# INNO_CAN_V1_1.net
KiCad netlist of a schematic drawn in EAGLE
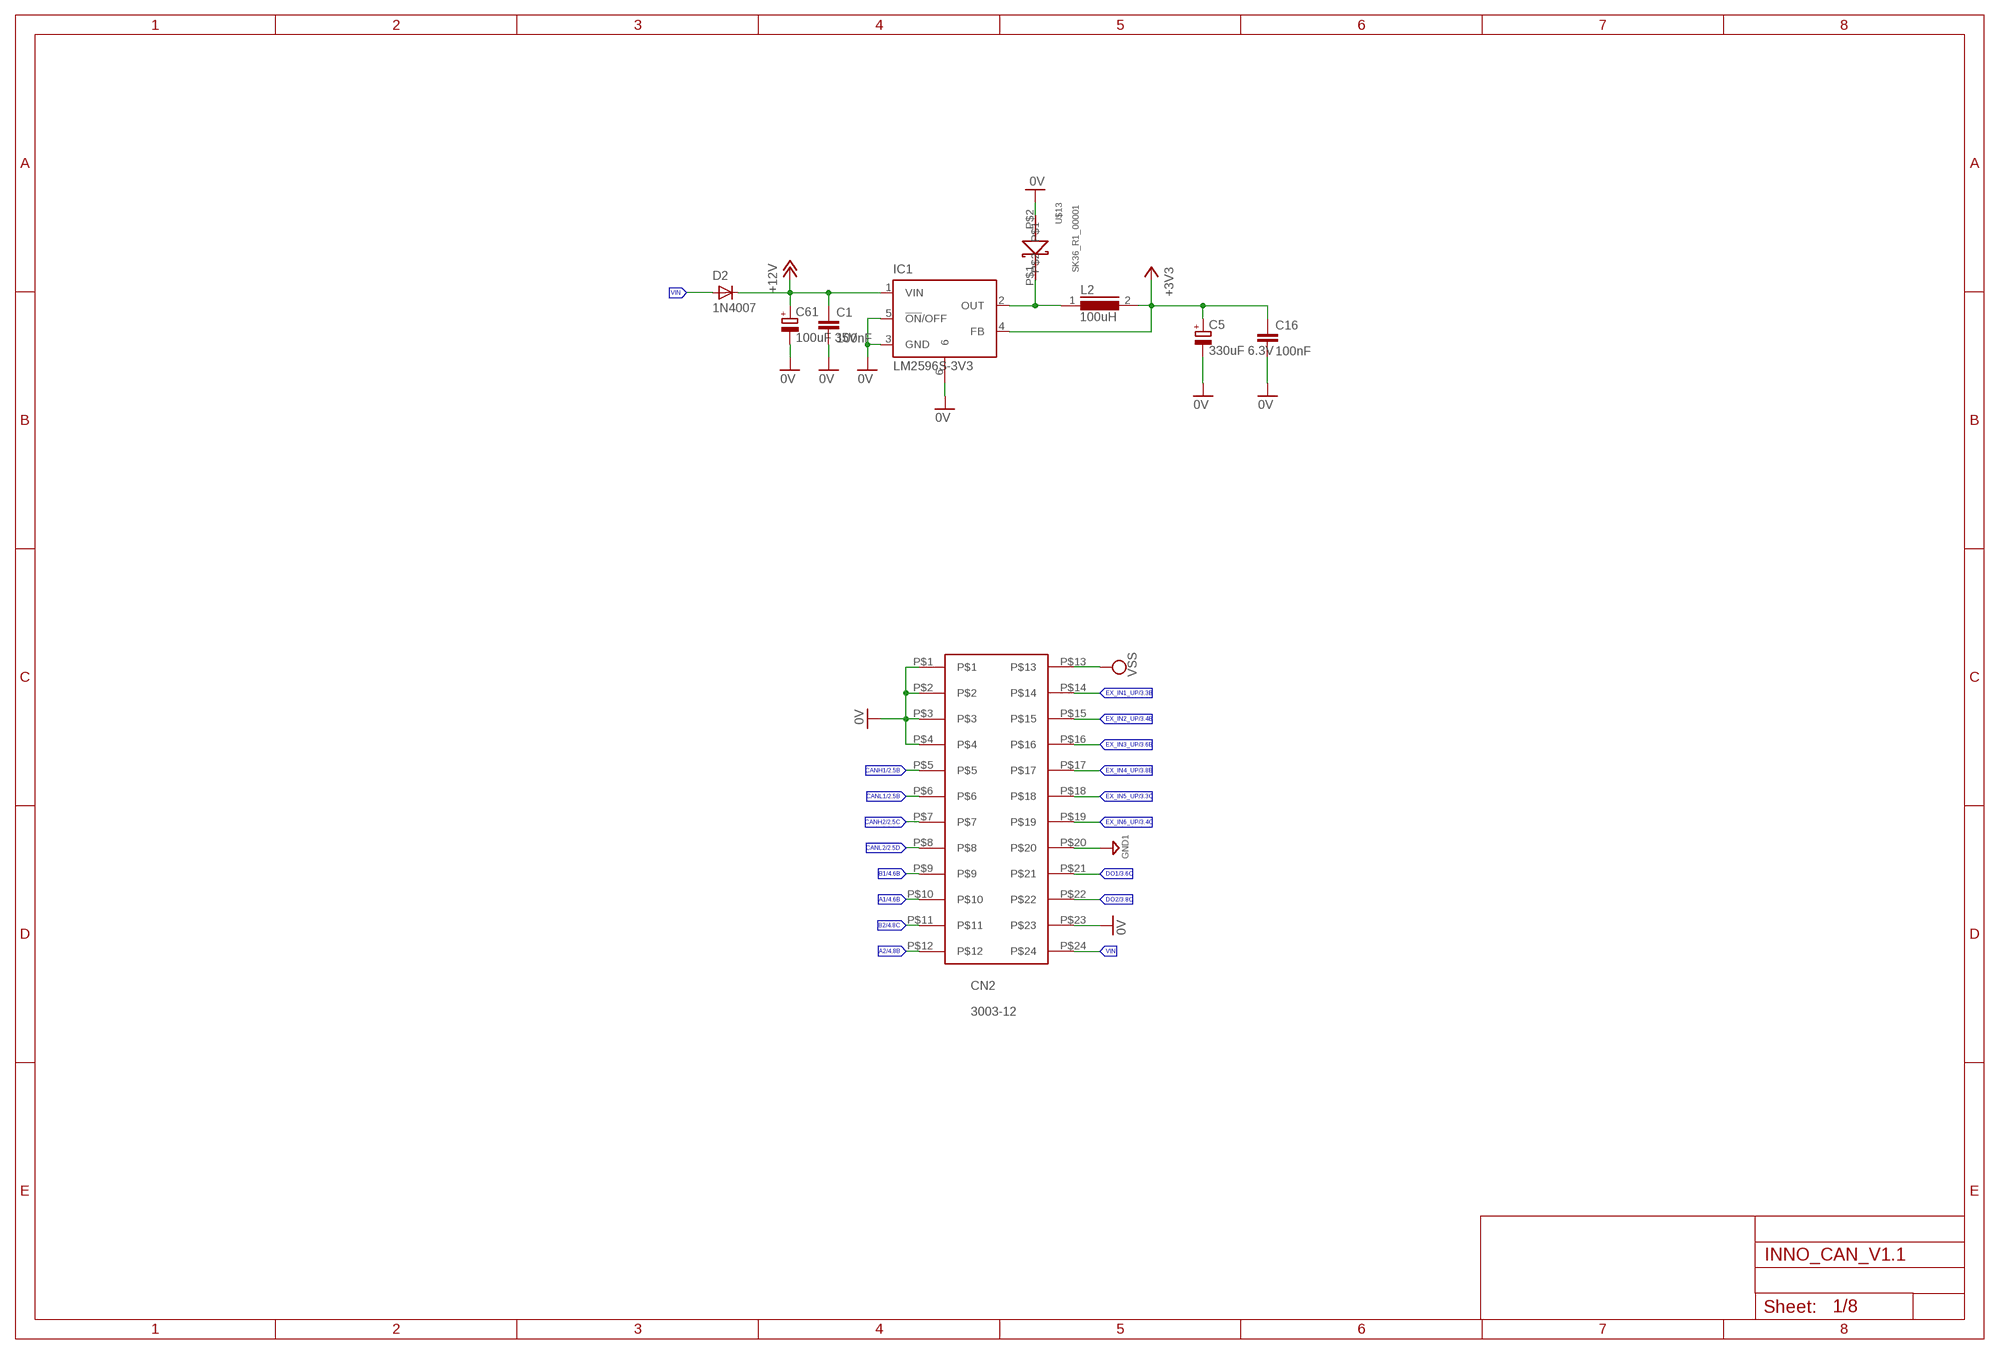
[diagram p0: schematic, sheet 1]
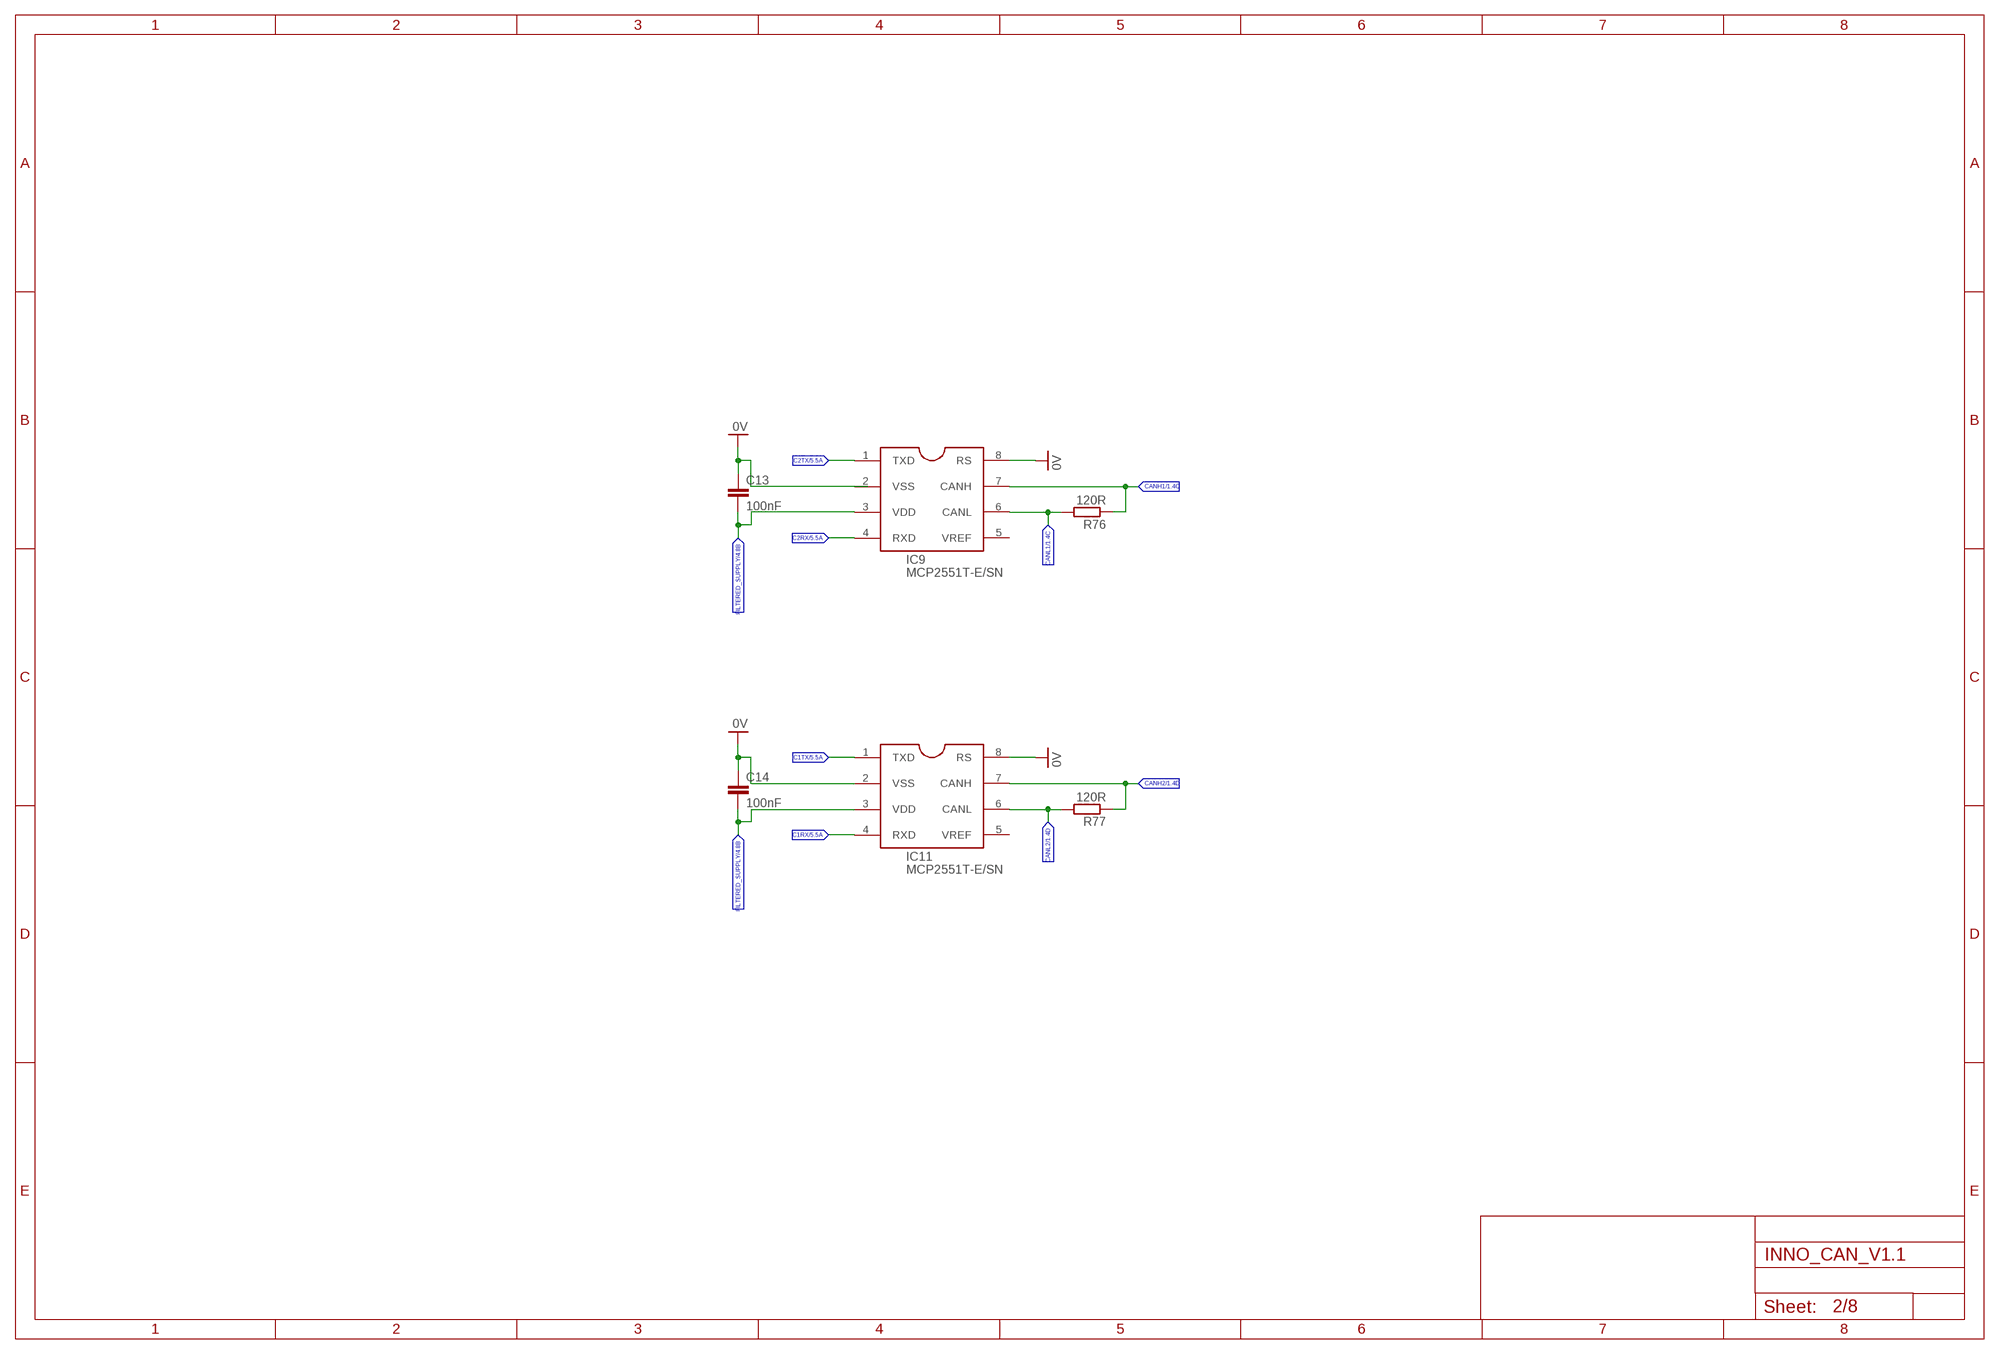
[diagram p1: schematic, sheet 2]
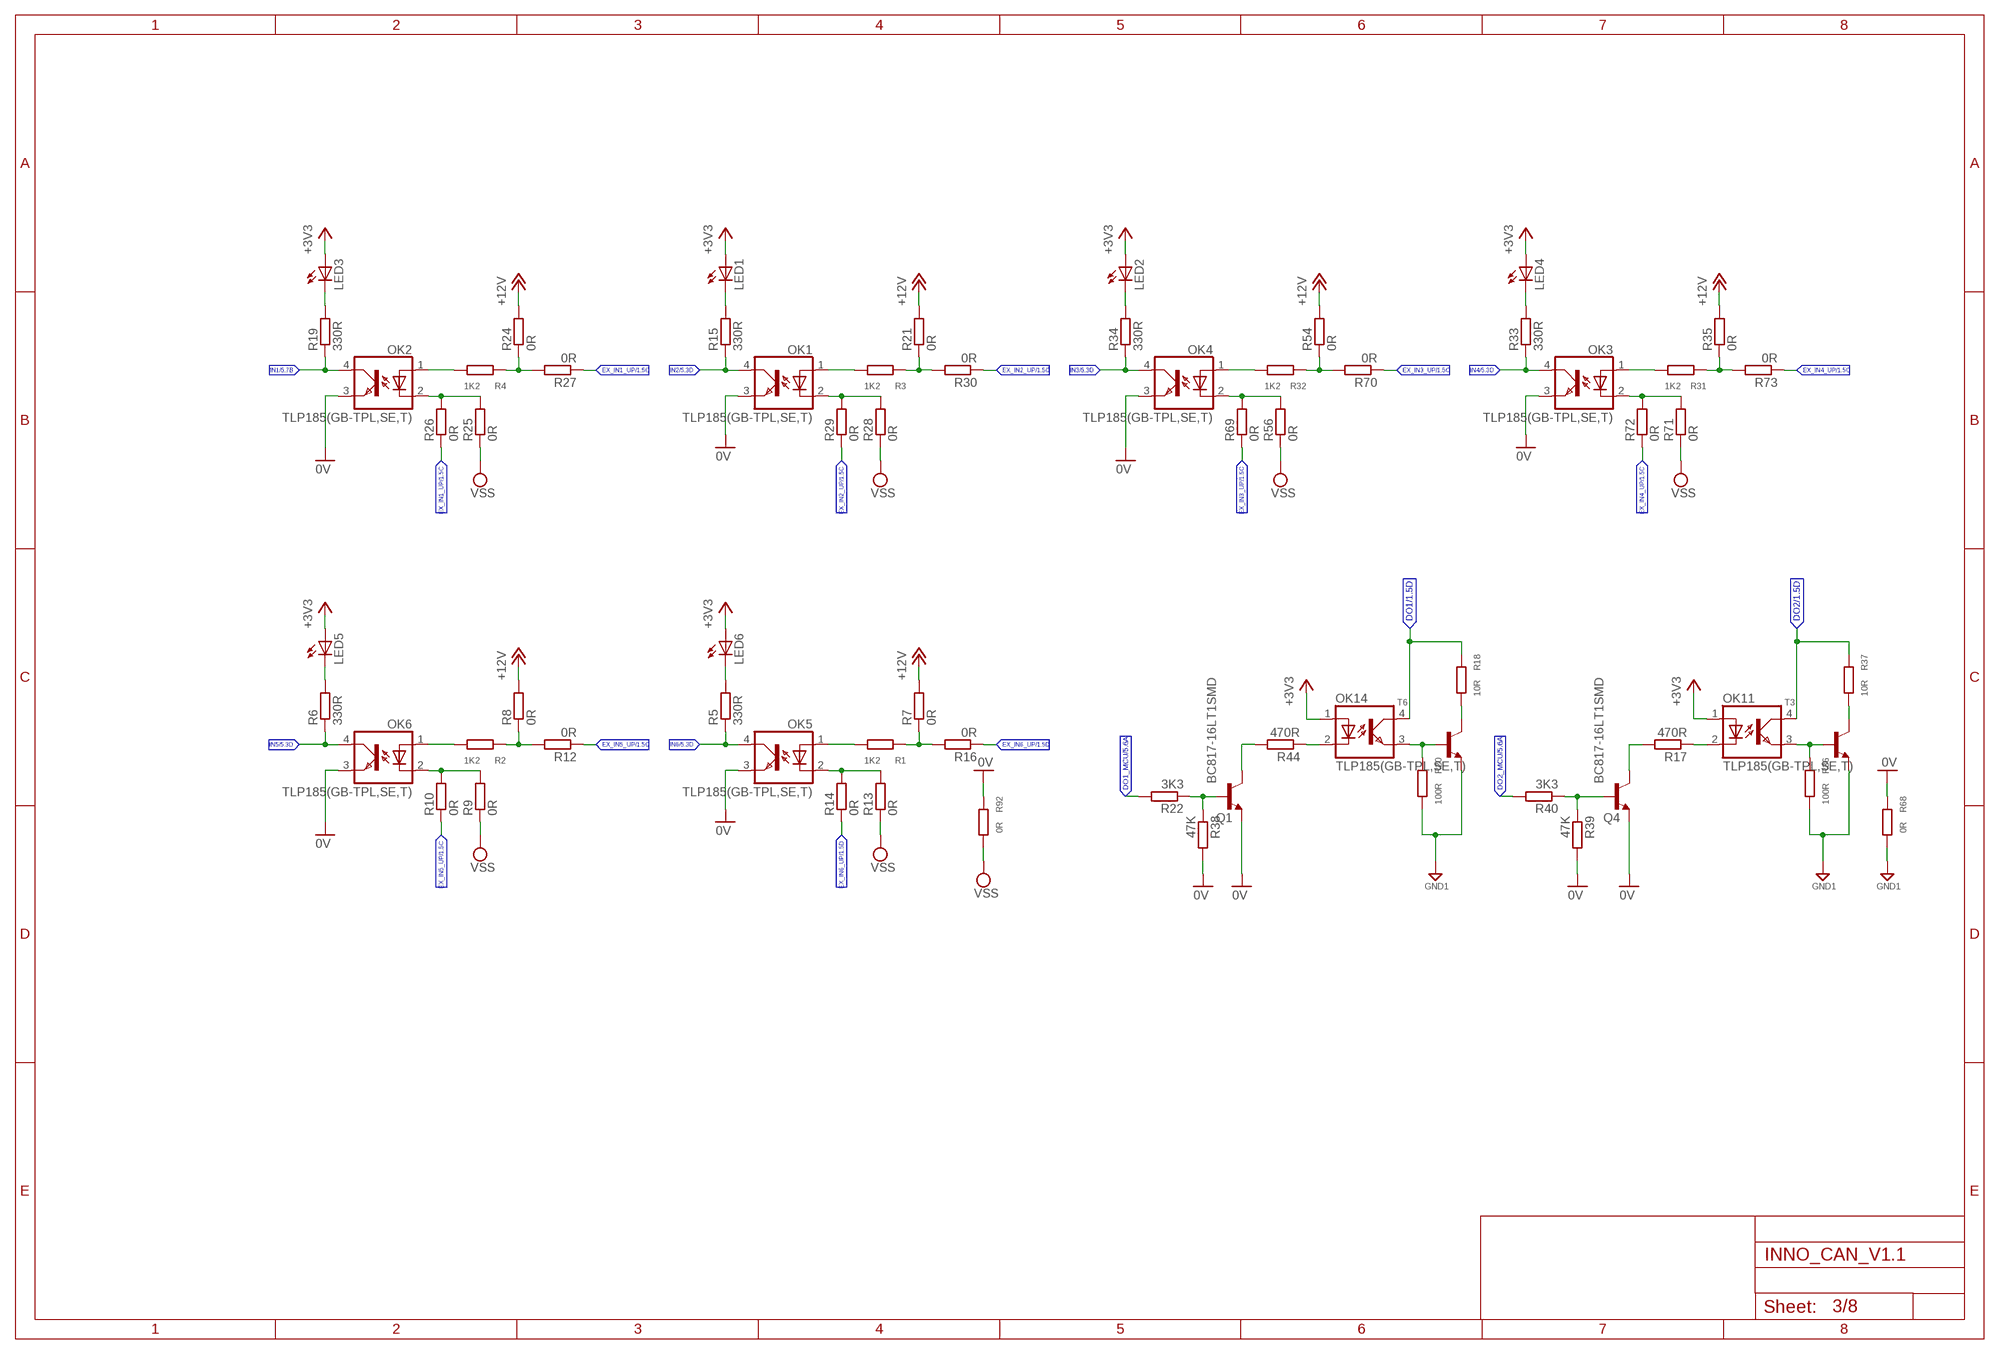
[diagram p2: schematic, sheet 3]
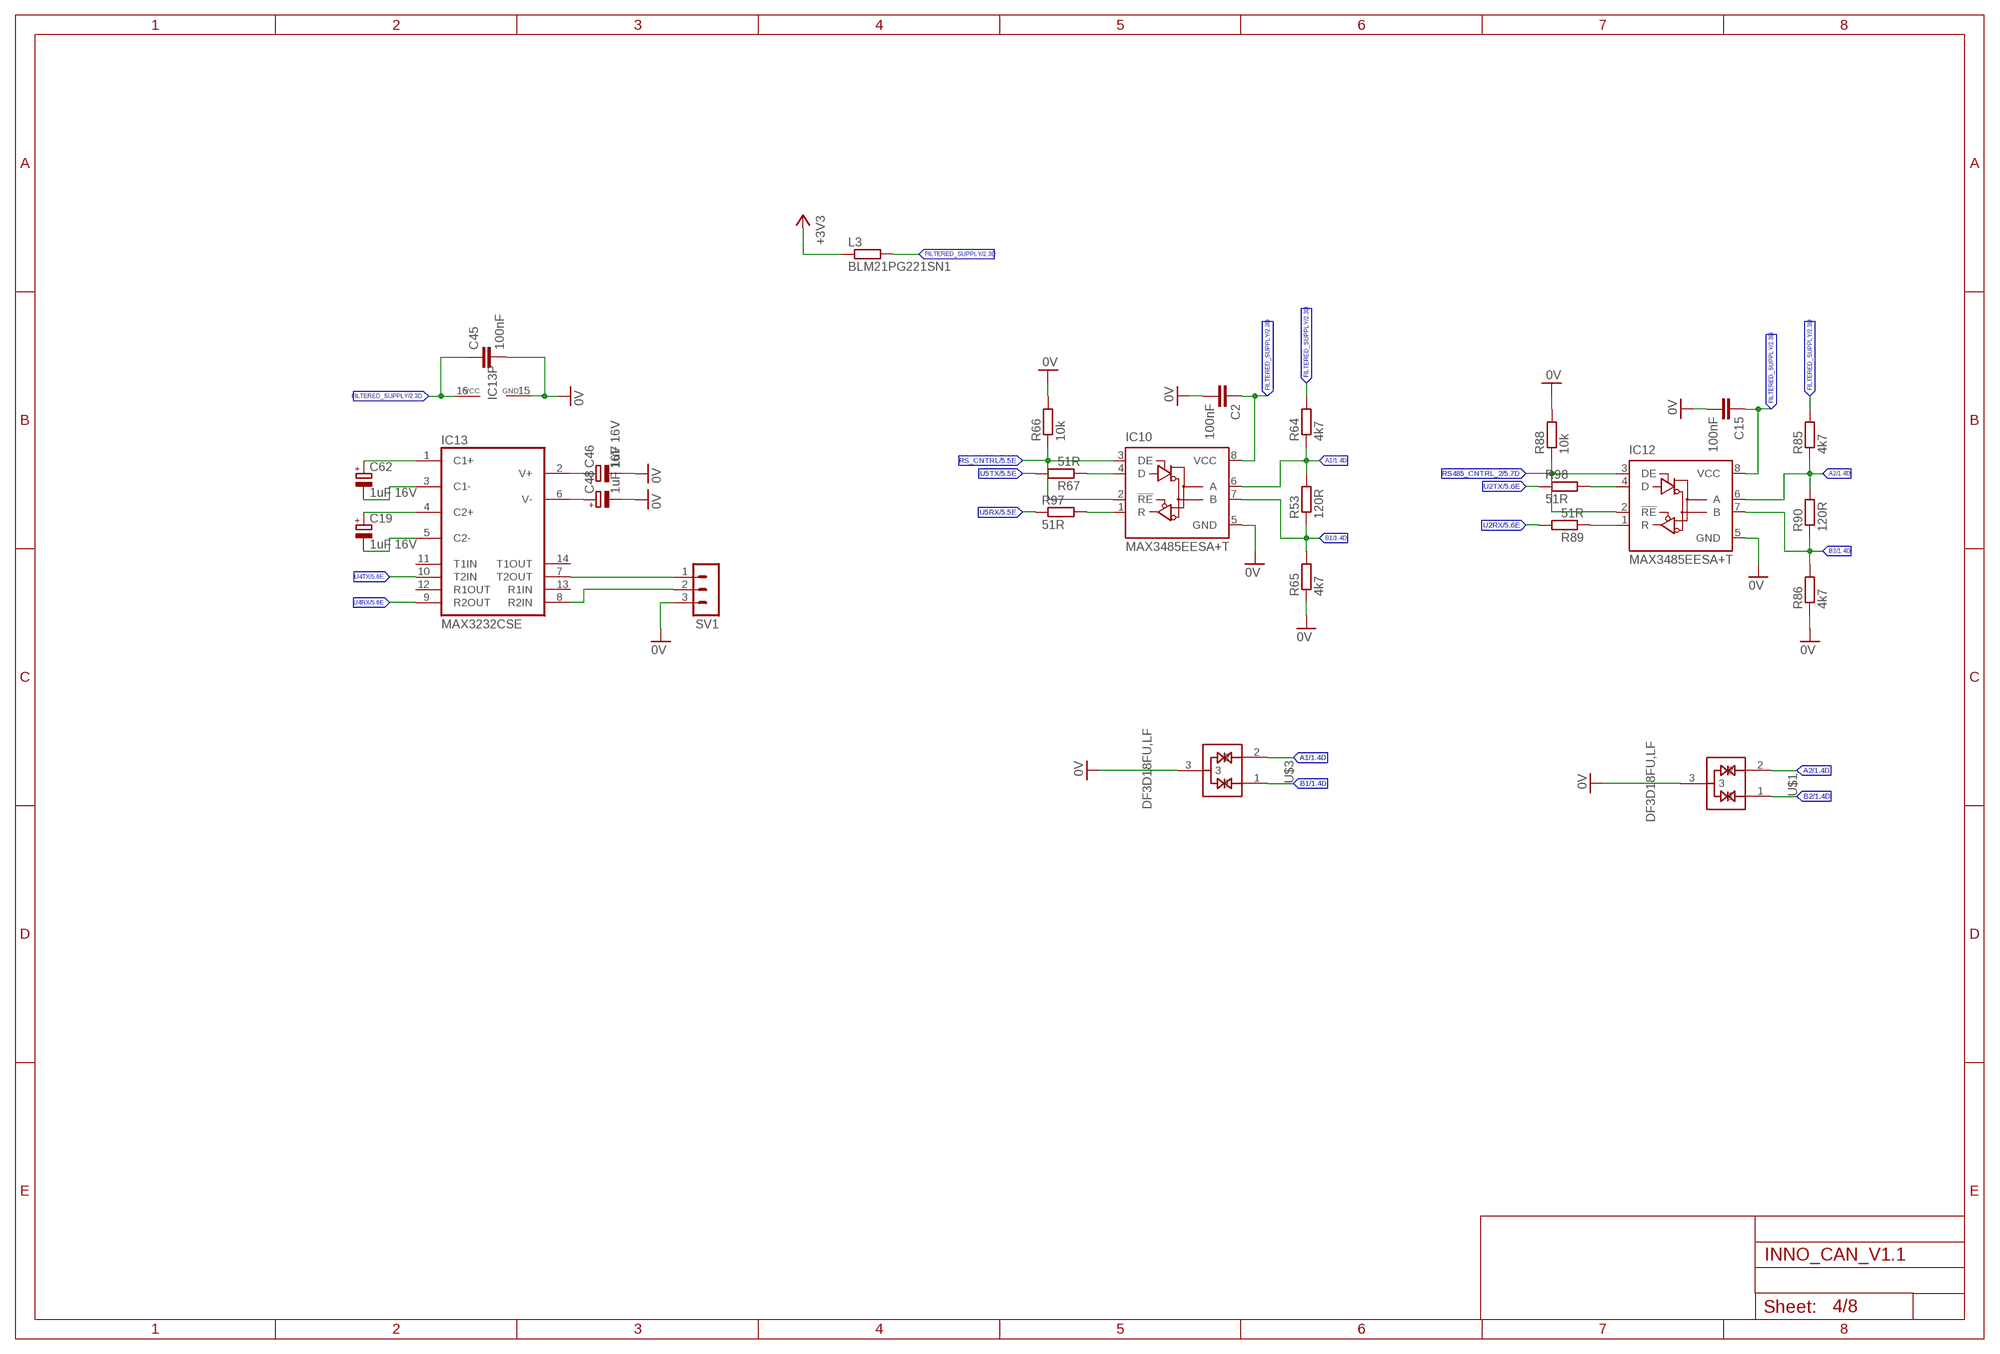
[diagram p3: schematic, sheet 4]
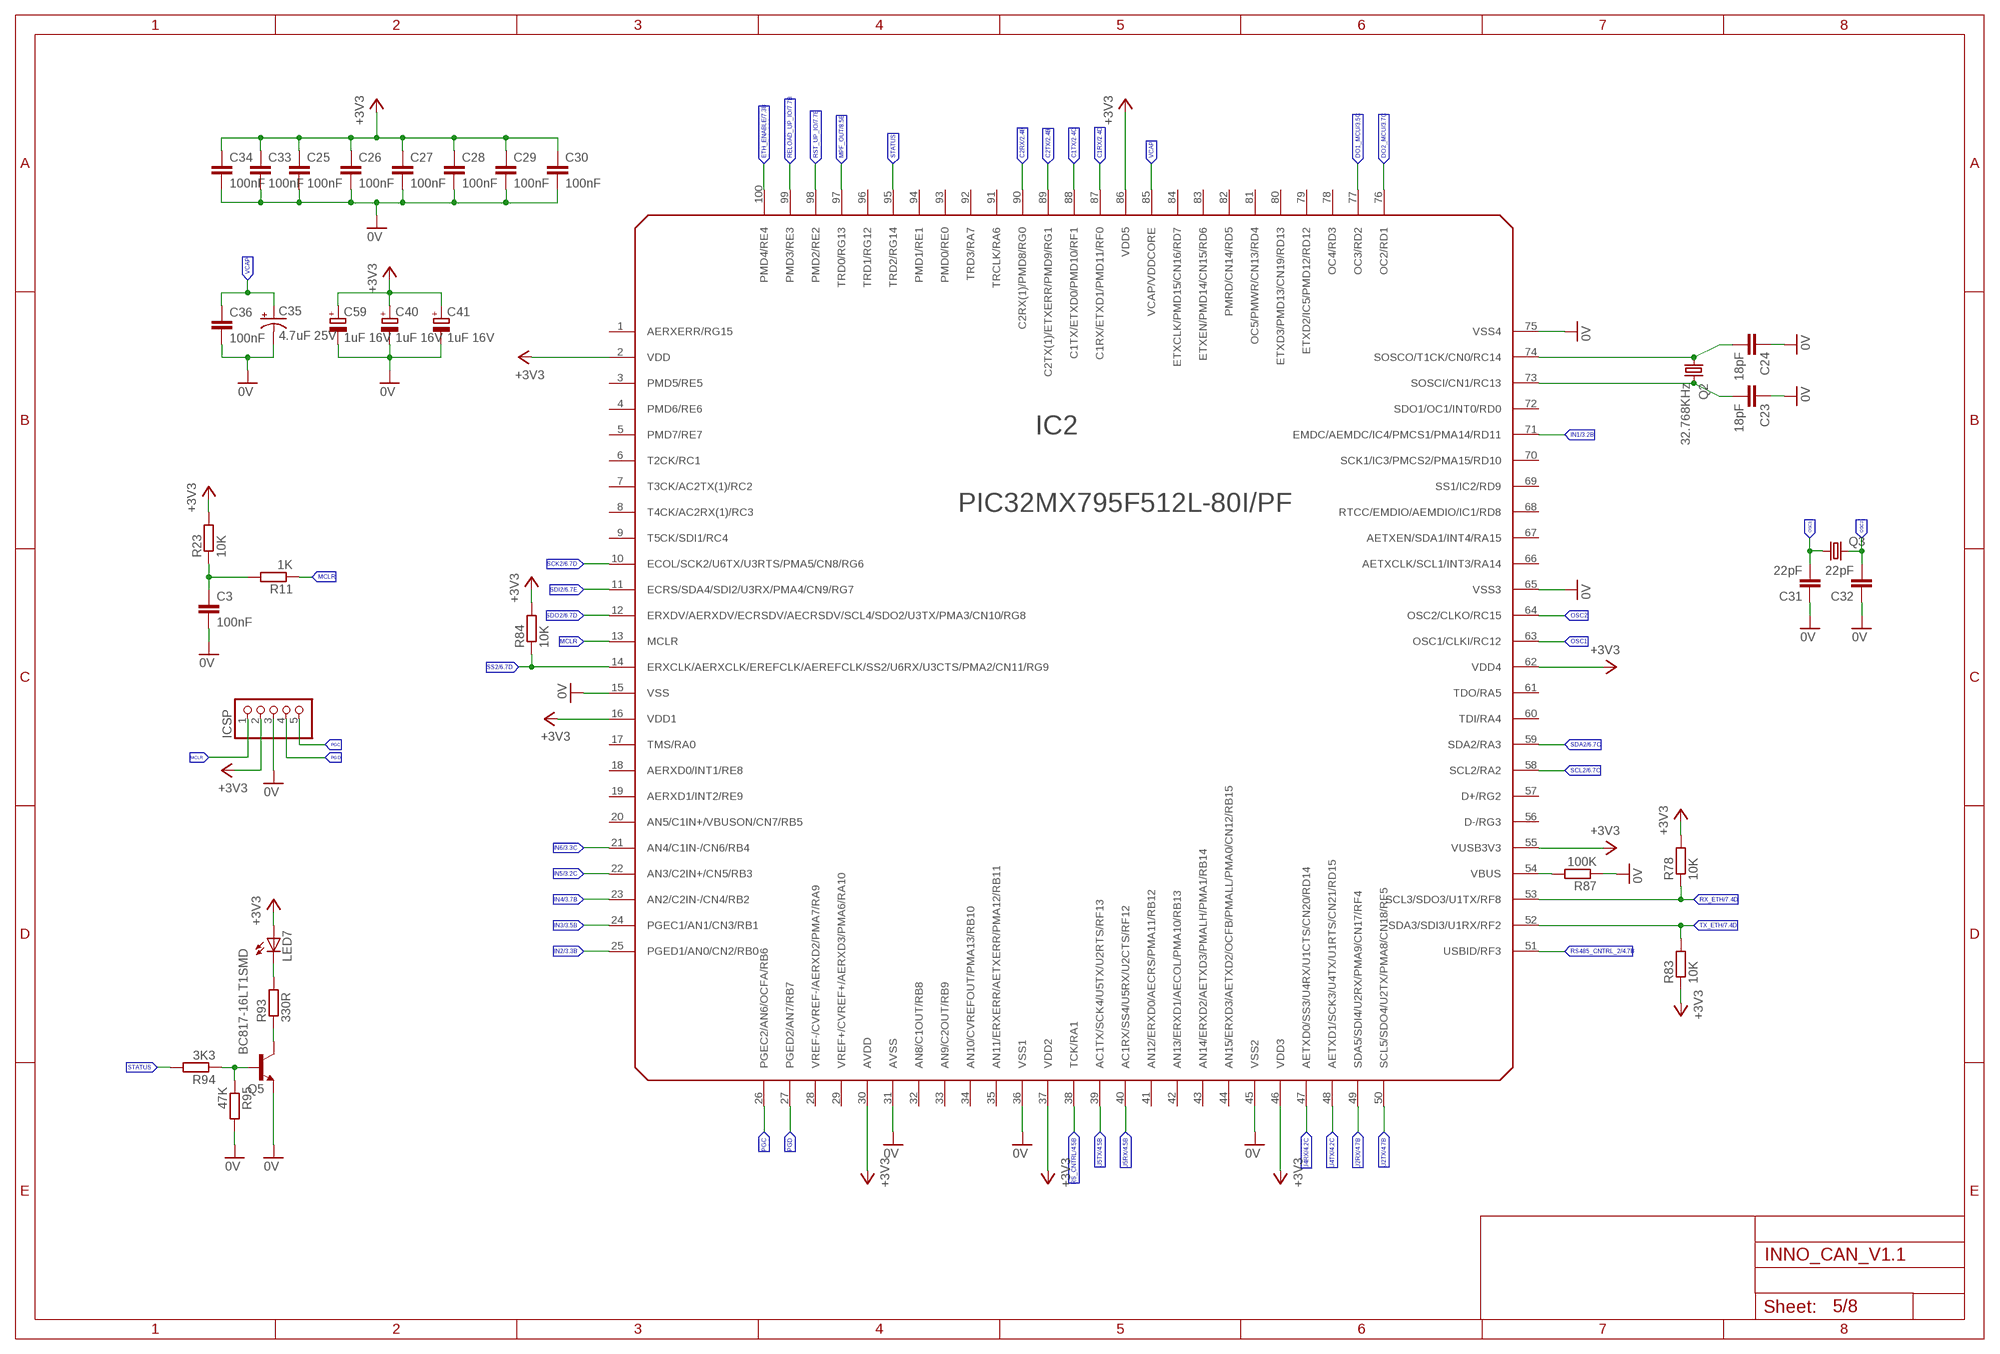
[diagram p4: schematic, sheet 5]
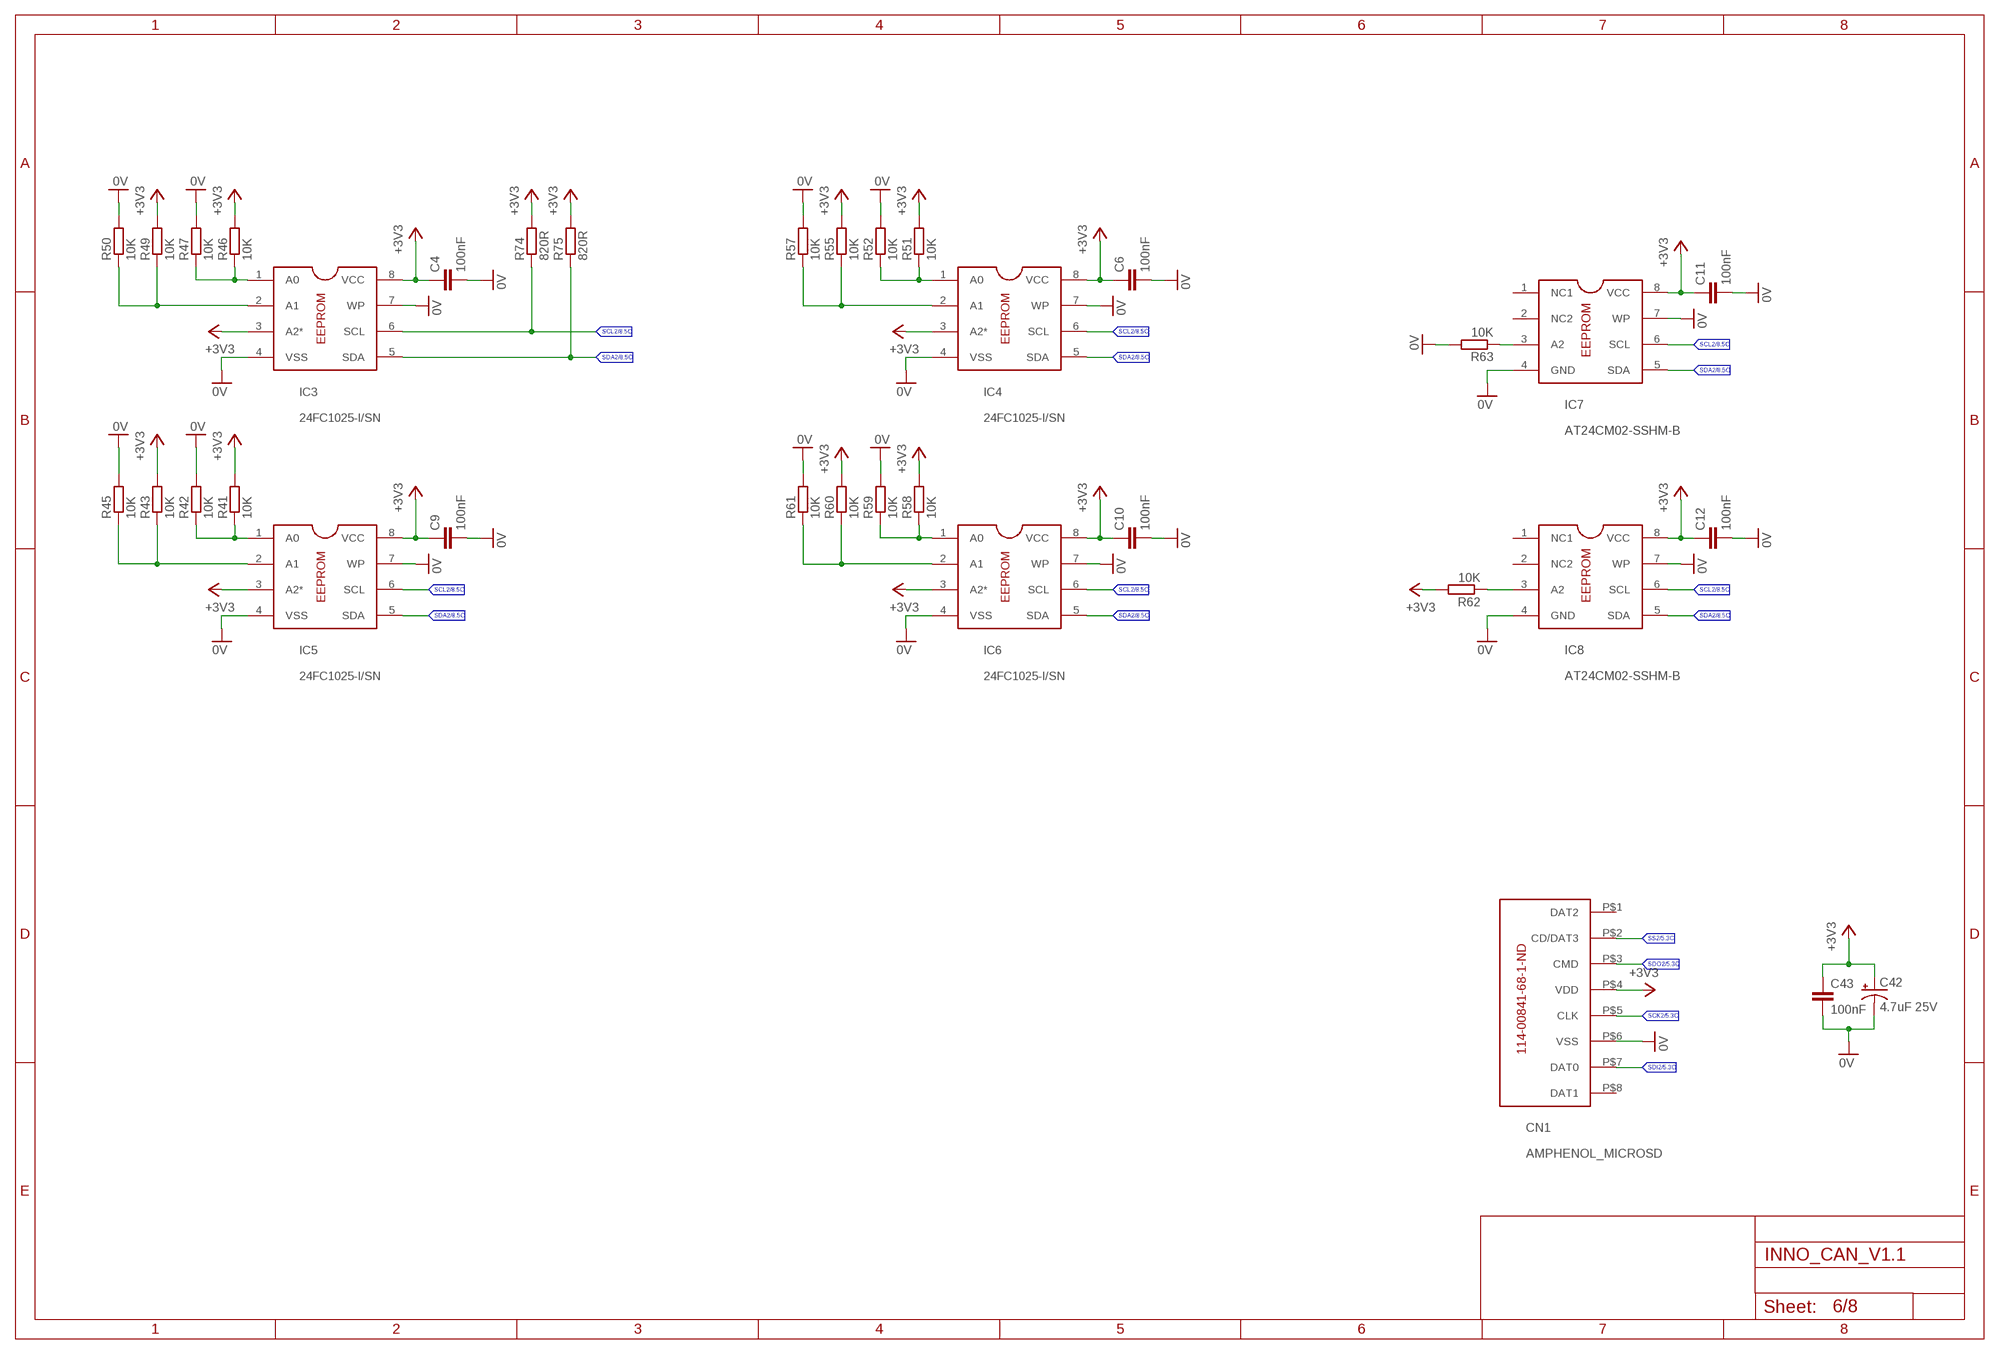
[diagram p5: schematic, sheet 6]
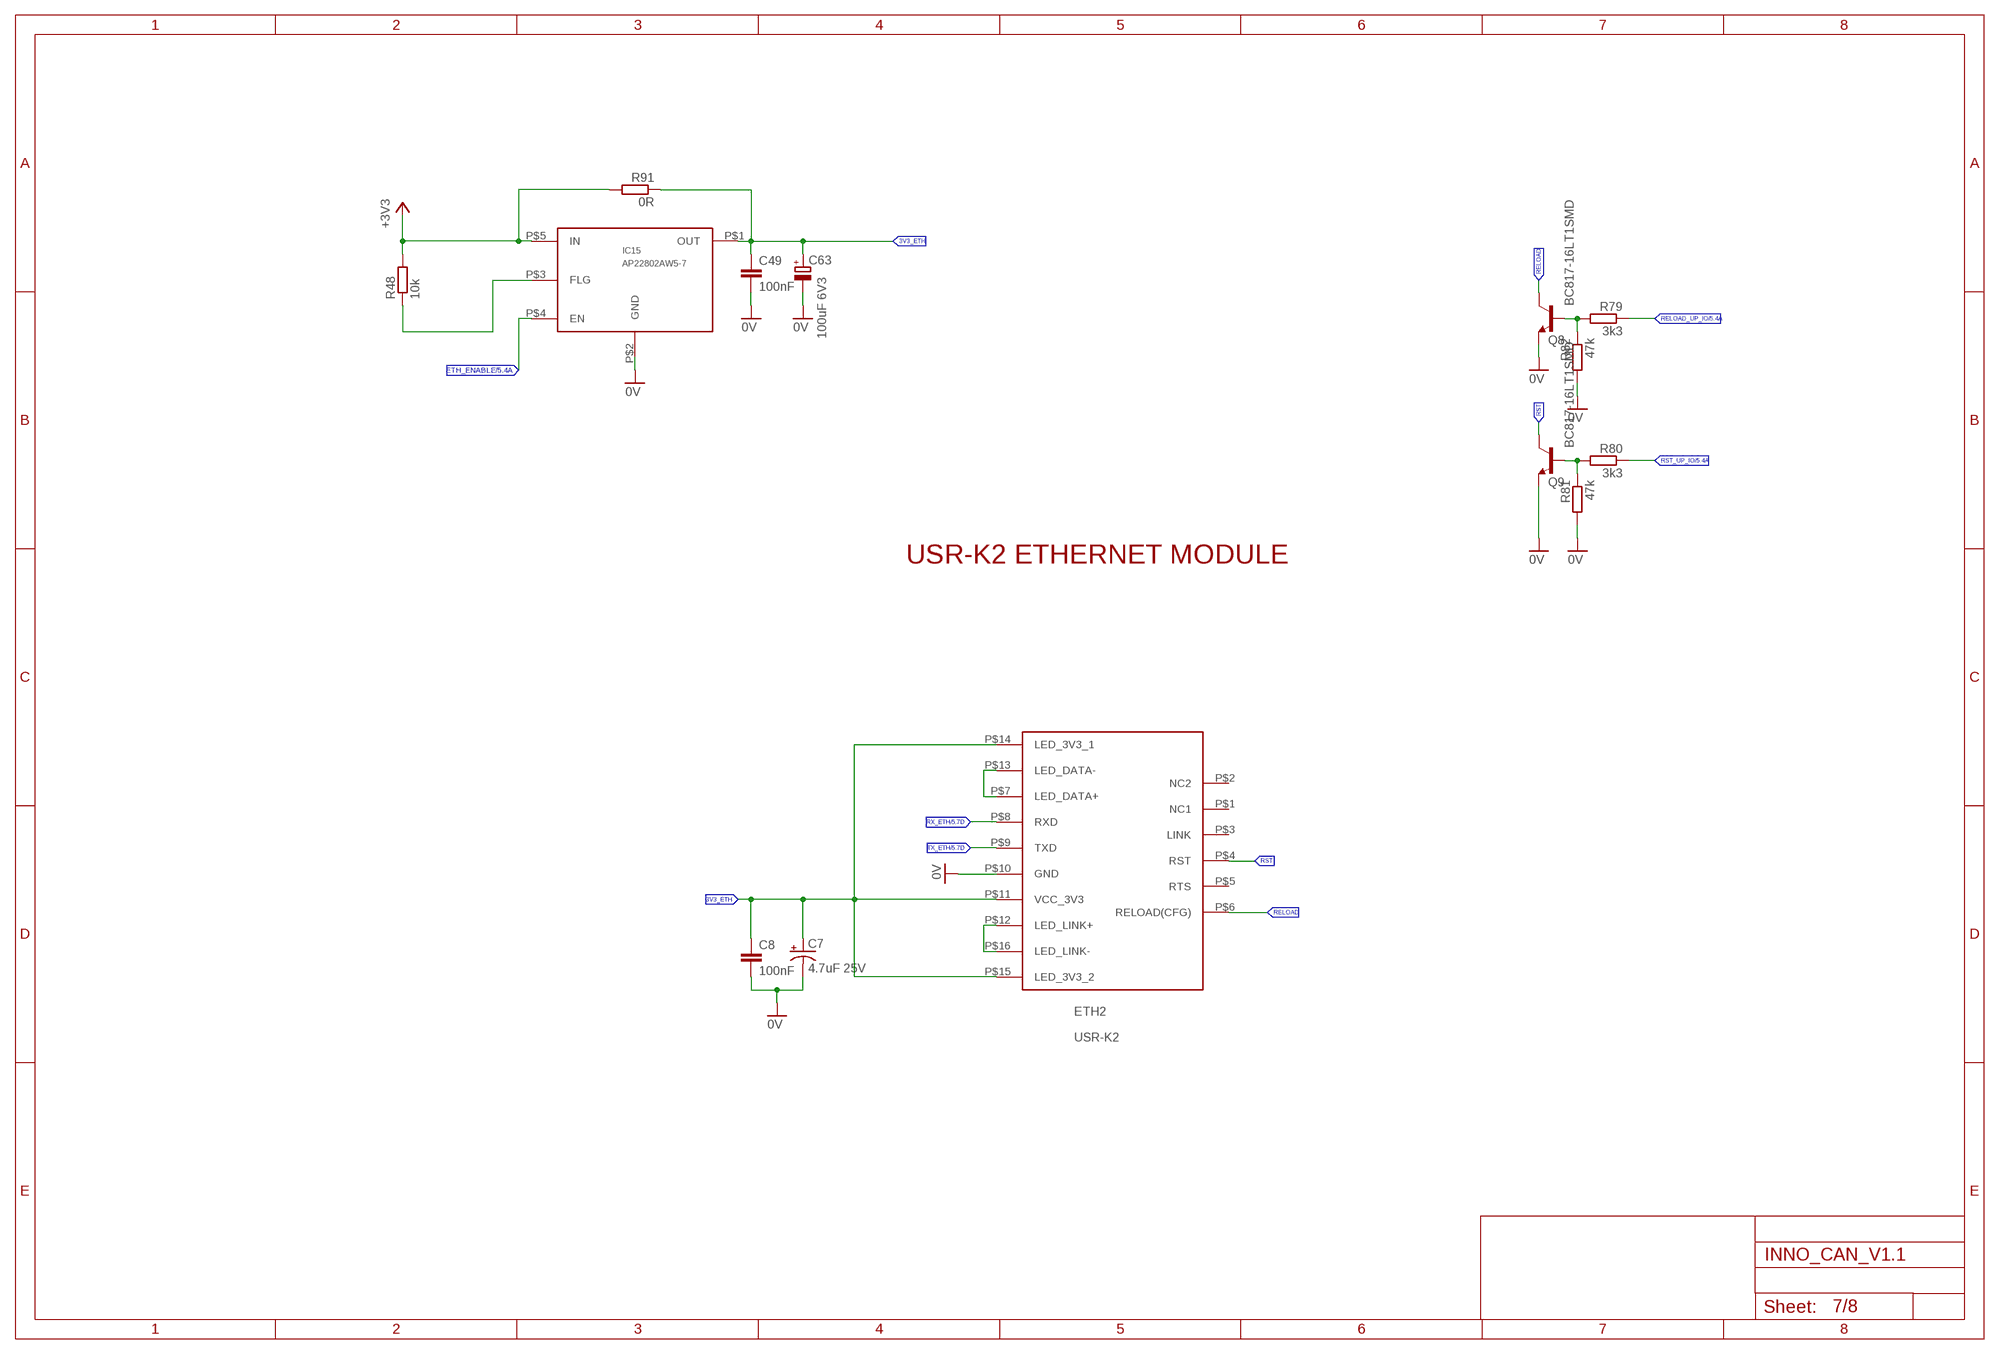
[diagram p6: schematic, sheet 7]
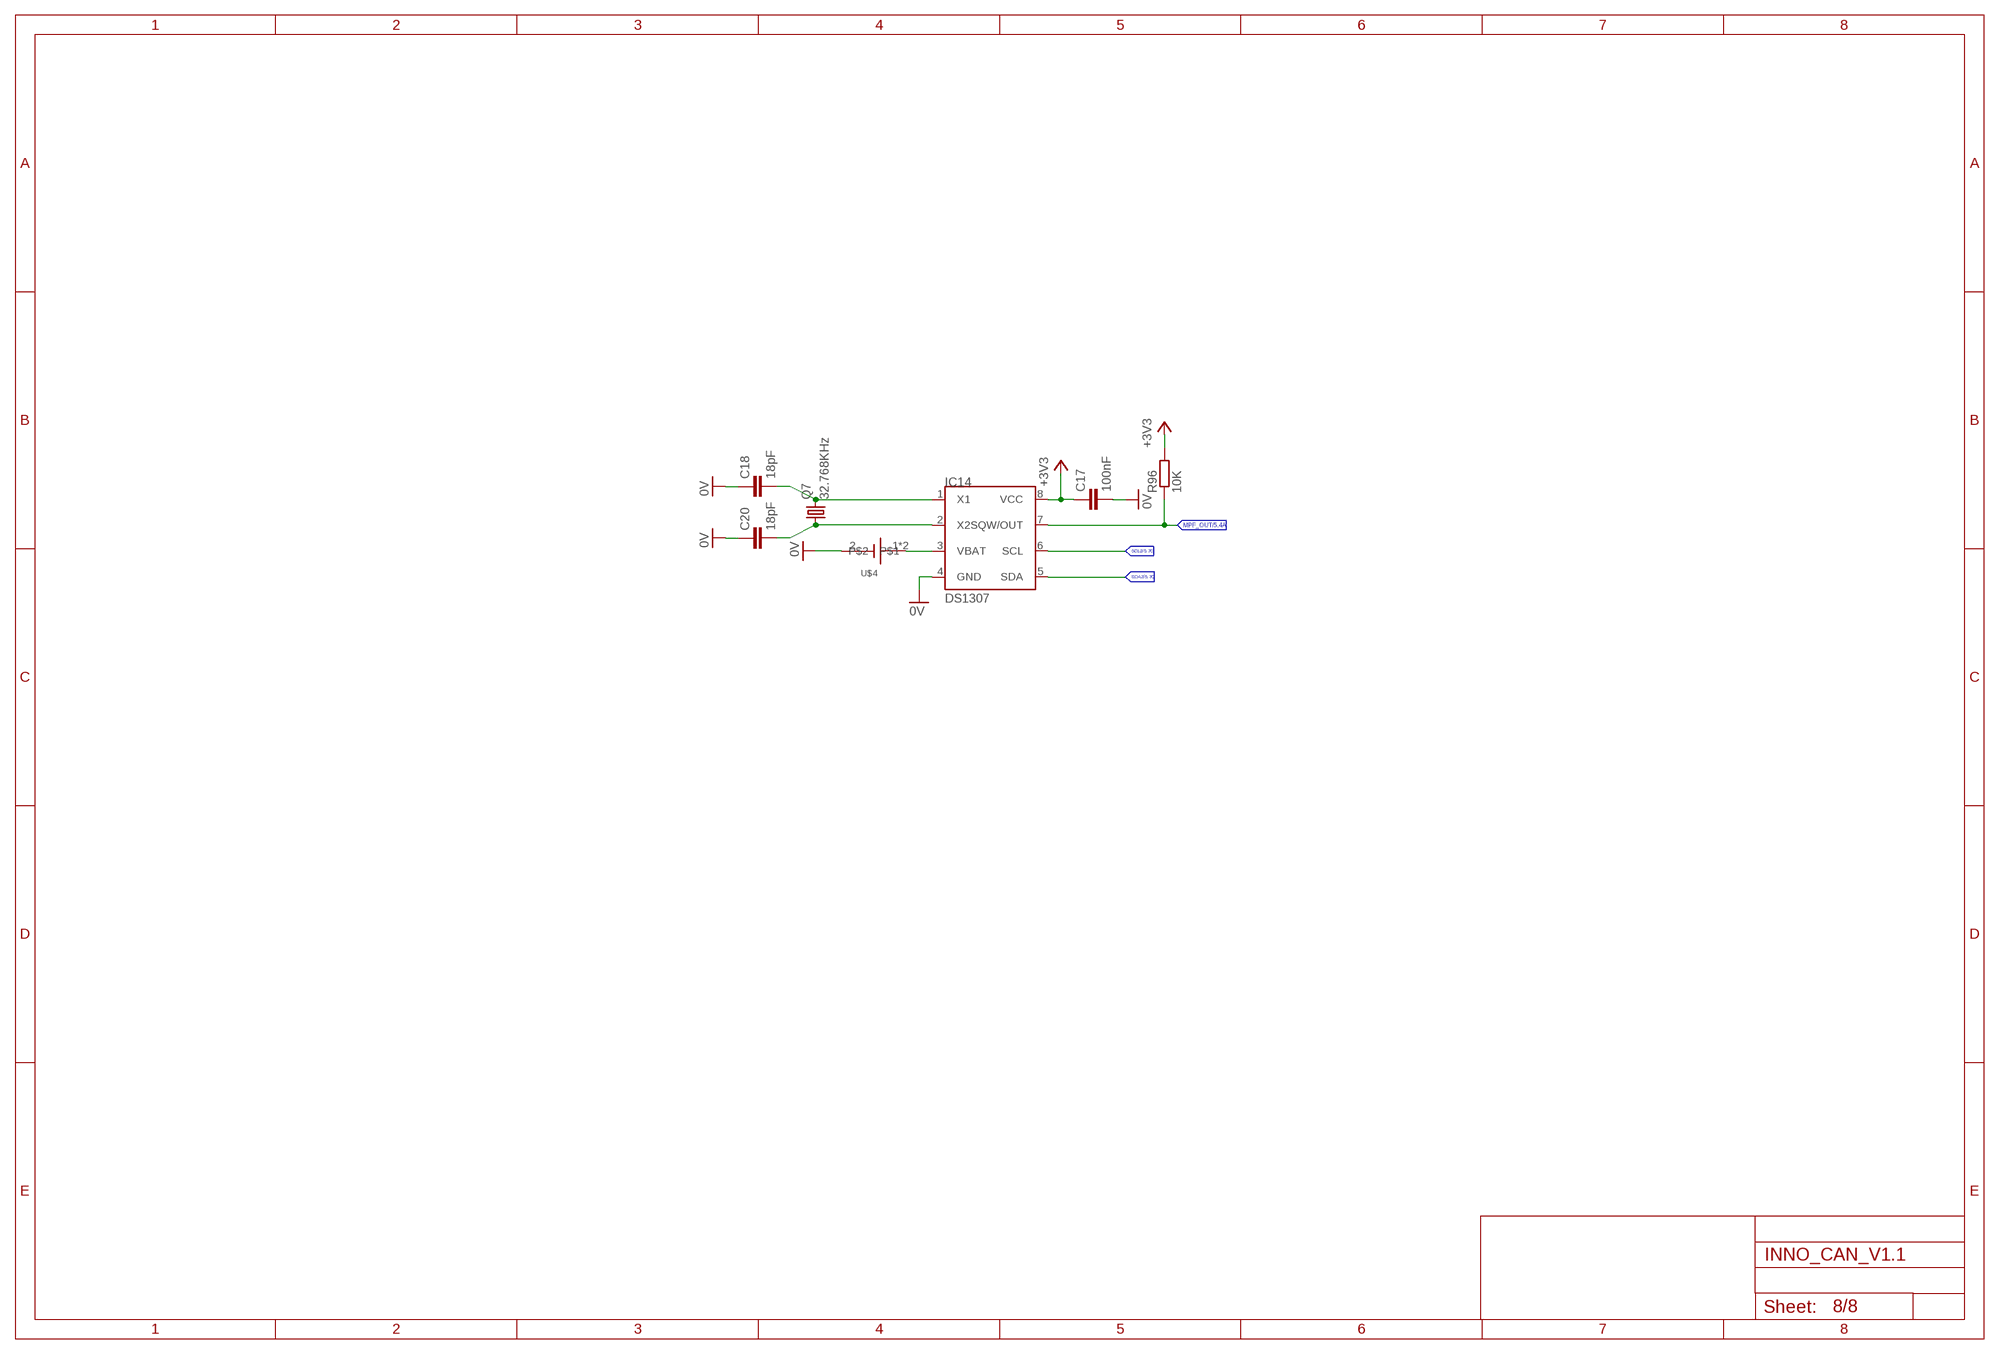
[diagram p7: schematic, sheet 8]

(export (version "E")
  (design (tool "Eeschema 10.0.6"))
  (components
    (comp (ref "C7")
      (value "4.7uF 25V")
      (footprint "eagle-import:A_3216-18R")
      (libsource (lib "eagle-import") (part "CPOL-USA/3216-18R"))
    )
    (comp (ref "C8")
      (value "100nF")
      (footprint "eagle-import:C0603")
      (libsource (lib "eagle-import") (part "C-EUC0603"))
    )
    (comp (ref "C49")
      (value "100nF")
      (footprint "eagle-import:C0603")
      (libsource (lib "eagle-import") (part "C-EUC0603"))
    )
    (comp (ref "C63")
      (value "100uF 6V3")
      (footprint "eagle-import:E5-5")
      (libsource (lib "eagle-import") (part "CPOL-EUE5-5"))
    )
    (comp (ref "ETH2")
      (value "USR-K2")
      (footprint "eagle-import:USR-K2")
      (libsource (lib "eagle-import") (part "USR-K2"))
    )
    (comp (ref "IC15")
      (value "AP22802AW5-7")
      (footprint "eagle-import:SOT23-5L")
      (libsource (lib "eagle-import") (part "AP22802AW5-7"))
    )
    (comp (ref "Q8")
      (value "BC817-16LT1SMD")
      (footprint "eagle-import:SOT23-BEC")
      (libsource (lib "eagle-import") (part "BC817SMD-16LT1"))
    )
    (comp (ref "Q9")
      (value "BC817-16LT1SMD")
      (footprint "eagle-import:SOT23-BEC")
      (libsource (lib "eagle-import") (part "BC817SMD-16LT1"))
    )
    (comp (ref "R48")
      (value "10k")
      (footprint "eagle-import:R0603")
      (libsource (lib "eagle-import") (part "R-EU_R0603"))
    )
    (comp (ref "R79")
      (value "3k3")
      (footprint "eagle-import:R0805")
      (libsource (lib "eagle-import") (part "R-EU_R0805"))
    )
    (comp (ref "R80")
      (value "3k3")
      (footprint "eagle-import:R0805")
      (libsource (lib "eagle-import") (part "R-EU_R0805"))
    )
    (comp (ref "R81")
      (value "47k")
      (footprint "eagle-import:R0805")
      (libsource (lib "eagle-import") (part "R-EU_R0805"))
    )
    (comp (ref "R82")
      (value "47k")
      (footprint "eagle-import:R0805")
      (libsource (lib "eagle-import") (part "R-EU_R0805"))
    )
    (comp (ref "R91")
      (value "0R")
      (footprint "eagle-import:R0805")
      (libsource (lib "eagle-import") (part "R-EU_R0805"))
    )
    (comp (ref "C3")
      (value "100nF")
      (footprint "eagle-import:C0603K")
      (libsource (lib "eagle-import") (part "C-EUC0603K"))
    )
    (comp (ref "C23")
      (value "18pF")
      (footprint "eagle-import:C0603")
      (libsource (lib "eagle-import") (part "C-EUC0603"))
    )
    (comp (ref "C24")
      (value "18pF")
      (footprint "eagle-import:C0603")
      (libsource (lib "eagle-import") (part "C-EUC0603"))
    )
    (comp (ref "C25")
      (value "100nF")
      (footprint "eagle-import:C0603K")
      (libsource (lib "eagle-import") (part "C-EUC0603K"))
    )
    (comp (ref "C26")
      (value "100nF")
      (footprint "eagle-import:C0603K")
      (libsource (lib "eagle-import") (part "C-EUC0603K"))
    )
    (comp (ref "C27")
      (value "100nF")
      (footprint "eagle-import:C0603K")
      (libsource (lib "eagle-import") (part "C-EUC0603K"))
    )
    (comp (ref "C28")
      (value "100nF")
      (footprint "eagle-import:C0603K")
      (libsource (lib "eagle-import") (part "C-EUC0603K"))
    )
    (comp (ref "C29")
      (value "100nF")
      (footprint "eagle-import:C0603K")
      (libsource (lib "eagle-import") (part "C-EUC0603K"))
    )
    (comp (ref "C30")
      (value "100nF")
      (footprint "eagle-import:C0603K")
      (libsource (lib "eagle-import") (part "C-EUC0603K"))
    )
    (comp (ref "C31")
      (value "22pF")
      (footprint "eagle-import:C0805")
      (libsource (lib "eagle-import") (part "C-EUC0805"))
    )
    (comp (ref "C32")
      (value "22pF")
      (footprint "eagle-import:C0805")
      (libsource (lib "eagle-import") (part "C-EUC0805"))
    )
    (comp (ref "C33")
      (value "100nF")
      (footprint "eagle-import:C0603K")
      (libsource (lib "eagle-import") (part "C-EUC0603K"))
    )
    (comp (ref "C34")
      (value "100nF")
      (footprint "eagle-import:C0603K")
      (libsource (lib "eagle-import") (part "C-EUC0603K"))
    )
    (comp (ref "C35")
      (value "4.7uF 25V")
      (footprint "eagle-import:A_3216-18R")
      (libsource (lib "eagle-import") (part "CPOL-USA/3216-18R"))
    )
    (comp (ref "C36")
      (value "100nF")
      (footprint "eagle-import:C0603")
      (libsource (lib "eagle-import") (part "C-EUC0603"))
    )
    (comp (ref "C40")
      (value "1uF 16V")
      (footprint "eagle-import:SMC_Z")
      (libsource (lib "eagle-import") (part "CPOL-EUSMCZ"))
    )
    (comp (ref "C41")
      (value "1uF 16V")
      (footprint "eagle-import:SMC_Z")
      (libsource (lib "eagle-import") (part "CPOL-EUSMCZ"))
    )
    (comp (ref "C59")
      (value "1uF 16V")
      (footprint "eagle-import:SMC_Z")
      (libsource (lib "eagle-import") (part "CPOL-EUSMCZ"))
    )
    (comp (ref "IC2")
      (value "PIC32MX795F512L-80I/PF")
      (footprint "eagle-import:TQFP100-14X14")
      (libsource (lib "eagle-import") (part "PIC32MX795F512L-80I/PF"))
    )
    (comp (ref "ICSP")
      (value "PINHD-1X5")
      (footprint "eagle-import:1X05")
      (libsource (lib "eagle-import") (part "PINHD-1X5"))
    )
    (comp (ref "LED7")
      (value "LEDCHIPLED_0805")
      (footprint "eagle-import:CHIPLED_0805")
      (libsource (lib "eagle-import") (part "LEDCHIPLED_0805"))
    )
    (comp (ref "Q2")
      (value "32.768KHz")
      (footprint "eagle-import:TC26V")
      (libsource (lib "eagle-import") (part "CRYSTALTC26V"))
    )
    (comp (ref "Q3")
      (value "CRYSTALHC49UP")
      (footprint "eagle-import:HC49UP")
      (libsource (lib "eagle-import") (part "CRYSTALHC49UP"))
    )
    (comp (ref "Q5")
      (value "BC817-16LT1SMD")
      (footprint "eagle-import:SOT23-BEC")
      (libsource (lib "eagle-import") (part "BC817SMD-16LT1"))
    )
    (comp (ref "R11")
      (value "1K")
      (footprint "eagle-import:R0603")
      (libsource (lib "eagle-import") (part "R-EU_R0603"))
    )
    (comp (ref "R23")
      (value "10K")
      (footprint "eagle-import:R0603")
      (libsource (lib "eagle-import") (part "R-EU_R0603"))
    )
    (comp (ref "R78")
      (value "10K")
      (footprint "eagle-import:R0603")
      (libsource (lib "eagle-import") (part "R-EU_R0603"))
    )
    (comp (ref "R83")
      (value "10K")
      (footprint "eagle-import:R0603")
      (libsource (lib "eagle-import") (part "R-EU_R0603"))
    )
    (comp (ref "R84")
      (value "10K")
      (footprint "eagle-import:R0603")
      (libsource (lib "eagle-import") (part "R-EU_R0603"))
    )
    (comp (ref "R87")
      (value "100K")
      (footprint "eagle-import:R0603")
      (libsource (lib "eagle-import") (part "R-EU_R0603"))
    )
    (comp (ref "R93")
      (value "330R")
      (footprint "eagle-import:R0603")
      (libsource (lib "eagle-import") (part "R-EU_R0603"))
    )
    (comp (ref "R94")
      (value "3K3")
      (footprint "eagle-import:R0603")
      (libsource (lib "eagle-import") (part "R-EU_R0603"))
    )
    (comp (ref "R95")
      (value "47K")
      (footprint "eagle-import:R0603")
      (libsource (lib "eagle-import") (part "R-EU_R0603"))
    )
    (comp (ref "C2")
      (value "100nF")
      (footprint "eagle-import:C0603")
      (libsource (lib "eagle-import") (part "C-EUC0603"))
    )
    (comp (ref "C15")
      (value "100nF")
      (footprint "eagle-import:C0603")
      (libsource (lib "eagle-import") (part "C-EUC0603"))
    )
    (comp (ref "C19")
      (value "1uF 16V")
      (footprint "eagle-import:SMC_Z")
      (libsource (lib "eagle-import") (part "CPOL-EUSMCZ"))
    )
    (comp (ref "C45")
      (value "100nF")
      (footprint "eagle-import:C0603")
      (libsource (lib "eagle-import") (part "C-EUC0603"))
    )
    (comp (ref "C46")
      (value "1uF 16V")
      (footprint "eagle-import:SMC_Z")
      (libsource (lib "eagle-import") (part "CPOL-EUSMCZ"))
    )
    (comp (ref "C48")
      (value "1uF 16V")
      (footprint "eagle-import:SMC_Z")
      (libsource (lib "eagle-import") (part "CPOL-EUSMCZ"))
    )
    (comp (ref "C62")
      (value "1uF 16V")
      (footprint "eagle-import:SMC_Z")
      (libsource (lib "eagle-import") (part "CPOL-EUSMCZ"))
    )
    (comp (ref "IC10")
      (value "MAX3485EESA+T")
      (footprint "eagle-import:D_R-PDSO-G8")
      (libsource (lib "eagle-import") (part "75176AD"))
    )
    (comp (ref "IC12")
      (value "MAX3485EESA+T")
      (footprint "eagle-import:D_R-PDSO-G8")
      (libsource (lib "eagle-import") (part "75176AD"))
    )
    (comp (ref "IC13")
      (value "MAX3232CSE")
      (footprint "eagle-import:SO16")
      (libsource (lib "eagle-import") (part "MAX3232SEC"))
    )
    (comp (ref "L3")
      (value "BLM21PG221SN1")
      (footprint "eagle-import:R0805")
      (libsource (lib "eagle-import") (part "R-EU_R0805"))
    )
    (comp (ref "R53")
      (value "120R")
      (footprint "eagle-import:R0603")
      (libsource (lib "eagle-import") (part "R-EU_R0603"))
    )
    (comp (ref "R64")
      (value "4k7")
      (footprint "eagle-import:R0603")
      (libsource (lib "eagle-import") (part "R-EU_R0603"))
    )
    (comp (ref "R65")
      (value "4k7")
      (footprint "eagle-import:R0603")
      (libsource (lib "eagle-import") (part "R-EU_R0603"))
    )
    (comp (ref "R66")
      (value "10k")
      (footprint "eagle-import:R0603")
      (libsource (lib "eagle-import") (part "R-EU_R0603"))
    )
    (comp (ref "R67")
      (value "51R")
      (footprint "eagle-import:R0603")
      (libsource (lib "eagle-import") (part "R-EU_R0603"))
    )
    (comp (ref "R85")
      (value "4k7")
      (footprint "eagle-import:R0603")
      (libsource (lib "eagle-import") (part "R-EU_R0603"))
    )
    (comp (ref "R86")
      (value "4k7")
      (footprint "eagle-import:R0603")
      (libsource (lib "eagle-import") (part "R-EU_R0603"))
    )
    (comp (ref "R88")
      (value "10k")
      (footprint "eagle-import:R0603")
      (libsource (lib "eagle-import") (part "R-EU_R0603"))
    )
    (comp (ref "R89")
      (value "51R")
      (footprint "eagle-import:R0603")
      (libsource (lib "eagle-import") (part "R-EU_R0603"))
    )
    (comp (ref "R90")
      (value "120R")
      (footprint "eagle-import:R0603")
      (libsource (lib "eagle-import") (part "R-EU_R0603"))
    )
    (comp (ref "R97")
      (value "51R")
      (footprint "eagle-import:R0603")
      (libsource (lib "eagle-import") (part "R-EU_R0603"))
    )
    (comp (ref "R98")
      (value "51R")
      (footprint "eagle-import:R0603")
      (libsource (lib "eagle-import") (part "R-EU_R0603"))
    )
    (comp (ref "SV1")
      (value "MA03-1")
      (footprint "eagle-import:MA03-1")
      (libsource (lib "eagle-import") (part "MA03-1"))
    )
    (comp (ref "U$1")
      (value "DF3D18FU,LF")
      (footprint "eagle-import:SOT323")
      (libsource (lib "eagle-import") (part "DF3D18FU,LF"))
    )
    (comp (ref "U$3")
      (value "DF3D18FU,LF")
      (footprint "eagle-import:SOT323")
      (libsource (lib "eagle-import") (part "DF3D18FU,LF"))
    )
    (comp (ref "C4")
      (value "100nF")
      (footprint "eagle-import:C0603")
      (libsource (lib "eagle-import") (part "C-EUC0603"))
    )
    (comp (ref "C6")
      (value "100nF")
      (footprint "eagle-import:C0603")
      (libsource (lib "eagle-import") (part "C-EUC0603"))
    )
    (comp (ref "C9")
      (value "100nF")
      (footprint "eagle-import:C0603")
      (libsource (lib "eagle-import") (part "C-EUC0603"))
    )
    (comp (ref "C10")
      (value "100nF")
      (footprint "eagle-import:C0603")
      (libsource (lib "eagle-import") (part "C-EUC0603"))
    )
    (comp (ref "C11")
      (value "100nF")
      (footprint "eagle-import:C0603")
      (libsource (lib "eagle-import") (part "C-EUC0603"))
    )
    (comp (ref "C12")
      (value "100nF")
      (footprint "eagle-import:C0603")
      (libsource (lib "eagle-import") (part "C-EUC0603"))
    )
    (comp (ref "C42")
      (value "4.7uF 25V")
      (footprint "eagle-import:A_3216-18R")
      (libsource (lib "eagle-import") (part "CPOL-USA/3216-18R"))
    )
    (comp (ref "C43")
      (value "100nF")
      (footprint "eagle-import:C0603")
      (libsource (lib "eagle-import") (part "C-EUC0603"))
    )
    (comp (ref "CN1")
      (value "AMPHENOL_MICROSD")
      (footprint "eagle-import:AMPHENOL_MICROSD")
      (libsource (lib "eagle-import") (part "AMPHENOL_MICROSD"))
    )
    (comp (ref "IC3")
      (value "24FC1025-I/SN")
      (footprint "eagle-import:SOIC08")
      (libsource (lib "eagle-import") (part "24FC1025-I/SN"))
    )
    (comp (ref "IC4")
      (value "24FC1025-I/SN")
      (footprint "eagle-import:SOIC08")
      (libsource (lib "eagle-import") (part "24FC1025-I/SN"))
    )
    (comp (ref "IC5")
      (value "24FC1025-I/SN")
      (footprint "eagle-import:SOIC08")
      (libsource (lib "eagle-import") (part "24FC1025-I/SN"))
    )
    (comp (ref "IC6")
      (value "24FC1025-I/SN")
      (footprint "eagle-import:SOIC08")
      (libsource (lib "eagle-import") (part "24FC1025-I/SN"))
    )
    (comp (ref "IC7")
      (value "AT24CM02-SSHM-B")
      (footprint "eagle-import:SOIC08")
      (libsource (lib "eagle-import") (part "AT24CM02-SSHM-B"))
    )
    (comp (ref "IC8")
      (value "AT24CM02-SSHM-B")
      (footprint "eagle-import:SOIC08")
      (libsource (lib "eagle-import") (part "AT24CM02-SSHM-B"))
    )
    (comp (ref "R41")
      (value "10K")
      (footprint "eagle-import:R0603")
      (libsource (lib "eagle-import") (part "R-EU_R0603"))
    )
    (comp (ref "R42")
      (value "10K")
      (footprint "eagle-import:R0603")
      (libsource (lib "eagle-import") (part "R-EU_R0603"))
    )
    (comp (ref "R43")
      (value "10K")
      (footprint "eagle-import:R0603")
      (libsource (lib "eagle-import") (part "R-EU_R0603"))
    )
    (comp (ref "R45")
      (value "10K")
      (footprint "eagle-import:R0603")
      (libsource (lib "eagle-import") (part "R-EU_R0603"))
    )
    (comp (ref "R46")
      (value "10K")
      (footprint "eagle-import:R0603")
      (libsource (lib "eagle-import") (part "R-EU_R0603"))
    )
    (comp (ref "R47")
      (value "10K")
      (footprint "eagle-import:R0603")
      (libsource (lib "eagle-import") (part "R-EU_R0603"))
    )
    (comp (ref "R49")
      (value "10K")
      (footprint "eagle-import:R0603")
      (libsource (lib "eagle-import") (part "R-EU_R0603"))
    )
    (comp (ref "R50")
      (value "10K")
      (footprint "eagle-import:R0603")
      (libsource (lib "eagle-import") (part "R-EU_R0603"))
    )
    (comp (ref "R51")
      (value "10K")
      (footprint "eagle-import:R0603")
      (libsource (lib "eagle-import") (part "R-EU_R0603"))
    )
    (comp (ref "R52")
      (value "10K")
      (footprint "eagle-import:R0603")
      (libsource (lib "eagle-import") (part "R-EU_R0603"))
    )
    (comp (ref "R55")
      (value "10K")
      (footprint "eagle-import:R0603")
      (libsource (lib "eagle-import") (part "R-EU_R0603"))
    )
    (comp (ref "R57")
      (value "10K")
      (footprint "eagle-import:R0603")
      (libsource (lib "eagle-import") (part "R-EU_R0603"))
    )
    (comp (ref "R58")
      (value "10K")
      (footprint "eagle-import:R0603")
      (libsource (lib "eagle-import") (part "R-EU_R0603"))
    )
    (comp (ref "R59")
      (value "10K")
      (footprint "eagle-import:R0603")
      (libsource (lib "eagle-import") (part "R-EU_R0603"))
    )
    (comp (ref "R60")
      (value "10K")
      (footprint "eagle-import:R0603")
      (libsource (lib "eagle-import") (part "R-EU_R0603"))
    )
    (comp (ref "R61")
      (value "10K")
      (footprint "eagle-import:R0603")
      (libsource (lib "eagle-import") (part "R-EU_R0603"))
    )
    (comp (ref "R62")
      (value "10K")
      (footprint "eagle-import:R0603")
      (libsource (lib "eagle-import") (part "R-EU_R0603"))
    )
    (comp (ref "R63")
      (value "10K")
      (footprint "eagle-import:R0603")
      (libsource (lib "eagle-import") (part "R-EU_R0603"))
    )
    (comp (ref "R74")
      (value "820R")
      (footprint "eagle-import:R0603")
      (libsource (lib "eagle-import") (part "R-EU_R0603"))
    )
    (comp (ref "R75")
      (value "820R")
      (footprint "eagle-import:R0603")
      (libsource (lib "eagle-import") (part "R-EU_R0603"))
    )
    (comp (ref "LED1")
      (value "LEDCHIPLED_0805")
      (footprint "eagle-import:CHIPLED_0805")
      (libsource (lib "eagle-import") (part "LEDCHIPLED_0805"))
    )
    (comp (ref "LED2")
      (value "LEDCHIPLED_0805")
      (footprint "eagle-import:CHIPLED_0805")
      (libsource (lib "eagle-import") (part "LEDCHIPLED_0805"))
    )
    (comp (ref "LED3")
      (value "LEDCHIPLED_0805")
      (footprint "eagle-import:CHIPLED_0805")
      (libsource (lib "eagle-import") (part "LEDCHIPLED_0805"))
    )
    (comp (ref "LED4")
      (value "LEDCHIPLED_0805")
      (footprint "eagle-import:CHIPLED_0805")
      (libsource (lib "eagle-import") (part "LEDCHIPLED_0805"))
    )
    (comp (ref "LED5")
      (value "LEDCHIPLED_0805")
      (footprint "eagle-import:CHIPLED_0805")
      (libsource (lib "eagle-import") (part "LEDCHIPLED_0805"))
    )
    (comp (ref "LED6")
      (value "LEDCHIPLED_0805")
      (footprint "eagle-import:CHIPLED_0805")
      (libsource (lib "eagle-import") (part "LEDCHIPLED_0805"))
    )
    (comp (ref "OK1")
      (value "TLP185(GB-TPL,SE,T)")
      (footprint "eagle-import:SMD4")
      (libsource (lib "eagle-import") (part "LTV816S"))
    )
    (comp (ref "OK2")
      (value "TLP185(GB-TPL,SE,T)")
      (footprint "eagle-import:SMD4")
      (libsource (lib "eagle-import") (part "LTV816S"))
    )
    (comp (ref "OK3")
      (value "TLP185(GB-TPL,SE,T)")
      (footprint "eagle-import:SMD4")
      (libsource (lib "eagle-import") (part "LTV816S"))
    )
    (comp (ref "OK4")
      (value "TLP185(GB-TPL,SE,T)")
      (footprint "eagle-import:SMD4")
      (libsource (lib "eagle-import") (part "LTV816S"))
    )
    (comp (ref "OK5")
      (value "TLP185(GB-TPL,SE,T)")
      (footprint "eagle-import:SMD4")
      (libsource (lib "eagle-import") (part "LTV816S"))
    )
    (comp (ref "OK6")
      (value "TLP185(GB-TPL,SE,T)")
      (footprint "eagle-import:SMD4")
      (libsource (lib "eagle-import") (part "LTV816S"))
    )
    (comp (ref "OK11")
      (value "TLP185(GB-TPL,SE,T)")
      (footprint "eagle-import:SMD4")
      (libsource (lib "eagle-import") (part "LTV816S"))
    )
    (comp (ref "OK14")
      (value "TLP185(GB-TPL,SE,T)")
      (footprint "eagle-import:SMD4")
      (libsource (lib "eagle-import") (part "LTV816S"))
    )
    (comp (ref "Q1")
      (value "BC817-16LT1SMD")
      (footprint "eagle-import:SOT23-BEC")
      (libsource (lib "eagle-import") (part "BC817SMD-16LT1"))
    )
    (comp (ref "Q4")
      (value "BC817-16LT1SMD")
      (footprint "eagle-import:SOT23-BEC")
      (libsource (lib "eagle-import") (part "BC817SMD-16LT1"))
    )
    (comp (ref "R1")
      (value "1K2")
      (footprint "eagle-import:M0805")
      (libsource (lib "eagle-import") (part "R-EU_M0805"))
    )
    (comp (ref "R2")
      (value "1K2")
      (footprint "eagle-import:M0805")
      (libsource (lib "eagle-import") (part "R-EU_M0805"))
    )
    (comp (ref "R3")
      (value "1K2")
      (footprint "eagle-import:M0805")
      (libsource (lib "eagle-import") (part "R-EU_M0805"))
    )
    (comp (ref "R4")
      (value "1K2")
      (footprint "eagle-import:M0805")
      (libsource (lib "eagle-import") (part "R-EU_M0805"))
    )
    (comp (ref "R5")
      (value "330R")
      (footprint "eagle-import:R0603")
      (libsource (lib "eagle-import") (part "R-EU_R0603"))
    )
    (comp (ref "R6")
      (value "330R")
      (footprint "eagle-import:R0603")
      (libsource (lib "eagle-import") (part "R-EU_R0603"))
    )
    (comp (ref "R7")
      (value "0R")
      (footprint "eagle-import:R0603")
      (libsource (lib "eagle-import") (part "R-EU_R0603"))
    )
    (comp (ref "R8")
      (value "0R")
      (footprint "eagle-import:R0603")
      (libsource (lib "eagle-import") (part "R-EU_R0603"))
    )
    (comp (ref "R9")
      (value "0R")
      (footprint "eagle-import:R0603")
      (libsource (lib "eagle-import") (part "R-EU_R0603"))
    )
    (comp (ref "R10")
      (value "0R")
      (footprint "eagle-import:R0603")
      (libsource (lib "eagle-import") (part "R-EU_R0603"))
    )
    (comp (ref "R12")
      (value "0R")
      (footprint "eagle-import:R0603")
      (libsource (lib "eagle-import") (part "R-EU_R0603"))
    )
    (comp (ref "R13")
      (value "0R")
      (footprint "eagle-import:R0603")
      (libsource (lib "eagle-import") (part "R-EU_R0603"))
    )
    (comp (ref "R14")
      (value "0R")
      (footprint "eagle-import:R0603")
      (libsource (lib "eagle-import") (part "R-EU_R0603"))
    )
    (comp (ref "R15")
      (value "330R")
      (footprint "eagle-import:R0603")
      (libsource (lib "eagle-import") (part "R-EU_R0603"))
    )
    (comp (ref "R16")
      (value "0R")
      (footprint "eagle-import:R0603")
      (libsource (lib "eagle-import") (part "R-EU_R0603"))
    )
    (comp (ref "R17")
      (value "470R")
      (footprint "eagle-import:R0603")
      (libsource (lib "eagle-import") (part "R-EU_R0603"))
    )
    (comp (ref "R18")
      (value "10R")
      (footprint "eagle-import:M0805")
      (libsource (lib "eagle-import") (part "R-EU_M0805"))
    )
    (comp (ref "R19")
      (value "330R")
      (footprint "eagle-import:R0603")
      (libsource (lib "eagle-import") (part "R-EU_R0603"))
    )
    (comp (ref "R20")
      (value "100R")
      (footprint "eagle-import:M0805")
      (libsource (lib "eagle-import") (part "R-EU_M0805"))
    )
    (comp (ref "R21")
      (value "0R")
      (footprint "eagle-import:R0603")
      (libsource (lib "eagle-import") (part "R-EU_R0603"))
    )
    (comp (ref "R22")
      (value "3K3")
      (footprint "eagle-import:R0603")
      (libsource (lib "eagle-import") (part "R-EU_R0603"))
    )
    (comp (ref "R24")
      (value "0R")
      (footprint "eagle-import:R0603")
      (libsource (lib "eagle-import") (part "R-EU_R0603"))
    )
    (comp (ref "R25")
      (value "0R")
      (footprint "eagle-import:R0603")
      (libsource (lib "eagle-import") (part "R-EU_R0603"))
    )
    (comp (ref "R26")
      (value "0R")
      (footprint "eagle-import:R0603")
      (libsource (lib "eagle-import") (part "R-EU_R0603"))
    )
    (comp (ref "R27")
      (value "0R")
      (footprint "eagle-import:R0603")
      (libsource (lib "eagle-import") (part "R-EU_R0603"))
    )
    (comp (ref "R28")
      (value "0R")
      (footprint "eagle-import:R0603")
      (libsource (lib "eagle-import") (part "R-EU_R0603"))
    )
    (comp (ref "R29")
      (value "0R")
      (footprint "eagle-import:R0603")
      (libsource (lib "eagle-import") (part "R-EU_R0603"))
    )
    (comp (ref "R30")
      (value "0R")
      (footprint "eagle-import:R0603")
      (libsource (lib "eagle-import") (part "R-EU_R0603"))
    )
    (comp (ref "R31")
      (value "1K2")
      (footprint "eagle-import:M0805")
      (libsource (lib "eagle-import") (part "R-EU_M0805"))
    )
    (comp (ref "R32")
      (value "1K2")
      (footprint "eagle-import:M0805")
      (libsource (lib "eagle-import") (part "R-EU_M0805"))
    )
    (comp (ref "R33")
      (value "330R")
      (footprint "eagle-import:R0603")
      (libsource (lib "eagle-import") (part "R-EU_R0603"))
    )
    (comp (ref "R34")
      (value "330R")
      (footprint "eagle-import:R0603")
      (libsource (lib "eagle-import") (part "R-EU_R0603"))
    )
    (comp (ref "R35")
      (value "0R")
      (footprint "eagle-import:R0603")
      (libsource (lib "eagle-import") (part "R-EU_R0603"))
    )
    (comp (ref "R36")
      (value "100R")
      (footprint "eagle-import:M0805")
      (libsource (lib "eagle-import") (part "R-EU_M0805"))
    )
    (comp (ref "R37")
      (value "10R")
      (footprint "eagle-import:M0805")
      (libsource (lib "eagle-import") (part "R-EU_M0805"))
    )
    (comp (ref "R38")
      (value "47K")
      (footprint "eagle-import:R0603")
      (libsource (lib "eagle-import") (part "R-EU_R0603"))
    )
    (comp (ref "R39")
      (value "47K")
      (footprint "eagle-import:R0603")
      (libsource (lib "eagle-import") (part "R-EU_R0603"))
    )
    (comp (ref "R40")
      (value "3K3")
      (footprint "eagle-import:R0603")
      (libsource (lib "eagle-import") (part "R-EU_R0603"))
    )
    (comp (ref "R44")
      (value "470R")
      (footprint "eagle-import:R0603")
      (libsource (lib "eagle-import") (part "R-EU_R0603"))
    )
    (comp (ref "R54")
      (value "0R")
      (footprint "eagle-import:R0603")
      (libsource (lib "eagle-import") (part "R-EU_R0603"))
    )
    (comp (ref "R56")
      (value "0R")
      (footprint "eagle-import:R0603")
      (libsource (lib "eagle-import") (part "R-EU_R0603"))
    )
    (comp (ref "R68")
      (value "0R")
      (footprint "eagle-import:M0805")
      (libsource (lib "eagle-import") (part "R-EU_M0805"))
    )
    (comp (ref "R69")
      (value "0R")
      (footprint "eagle-import:R0603")
      (libsource (lib "eagle-import") (part "R-EU_R0603"))
    )
    (comp (ref "R70")
      (value "0R")
      (footprint "eagle-import:R0603")
      (libsource (lib "eagle-import") (part "R-EU_R0603"))
    )
    (comp (ref "R71")
      (value "0R")
      (footprint "eagle-import:R0603")
      (libsource (lib "eagle-import") (part "R-EU_R0603"))
    )
    (comp (ref "R72")
      (value "0R")
      (footprint "eagle-import:R0603")
      (libsource (lib "eagle-import") (part "R-EU_R0603"))
    )
    (comp (ref "R73")
      (value "0R")
      (footprint "eagle-import:R0603")
      (libsource (lib "eagle-import") (part "R-EU_R0603"))
    )
    (comp (ref "R92")
      (value "0R")
      (footprint "eagle-import:M0805")
      (libsource (lib "eagle-import") (part "R-EU_M0805"))
    )
    (comp (ref "T3")
      (value "BC817-16LT1-NPN-SOT23-BEC")
      (footprint "eagle-import:SOT23-BEC")
      (libsource (lib "eagle-import") (part "-NPN-SOT23-BECBC817-16LT1"))
    )
    (comp (ref "T6")
      (value "BC817-16LT1-NPN-SOT23-BEC")
      (footprint "eagle-import:SOT23-BEC")
      (libsource (lib "eagle-import") (part "-NPN-SOT23-BECBC817-16LT1"))
    )
    (comp (ref "C17")
      (value "100nF")
      (footprint "eagle-import:C0603K")
      (libsource (lib "eagle-import") (part "C-EUC0603K"))
    )
    (comp (ref "C18")
      (value "18pF")
      (footprint "eagle-import:C0603")
      (libsource (lib "eagle-import") (part "C-EUC0603"))
    )
    (comp (ref "C20")
      (value "18pF")
      (footprint "eagle-import:C0603")
      (libsource (lib "eagle-import") (part "C-EUC0603"))
    )
    (comp (ref "IC14")
      (value "DS1307")
      (footprint "eagle-import:SOIC-8")
      (libsource (lib "eagle-import") (part "DS1307"))
    )
    (comp (ref "Q7")
      (value "32.768KHz")
      (footprint "eagle-import:TC26V")
      (libsource (lib "eagle-import") (part "CRYSTALTC26V"))
    )
    (comp (ref "R96")
      (value "10K")
      (footprint "eagle-import:R0603")
      (libsource (lib "eagle-import") (part "R-EU_R0603"))
    )
    (comp (ref "U$4")
      (value "BATTERY")
      (footprint "eagle-import:BATTERY")
      (libsource (lib "eagle-import") (part "BATTERY"))
    )
    (comp (ref "C1")
      (value "100nF")
      (footprint "eagle-import:C0603")
      (libsource (lib "eagle-import") (part "C-EUC0603"))
    )
    (comp (ref "C5")
      (value "330uF 6.3V")
      (footprint "eagle-import:E2,5-6")
      (libsource (lib "eagle-import") (part "CPOL-EUE2.5-6"))
    )
    (comp (ref "C16")
      (value "100nF")
      (footprint "eagle-import:C0603")
      (libsource (lib "eagle-import") (part "C-EUC0603"))
    )
    (comp (ref "C61")
      (value "100uF 35V")
      (footprint "eagle-import:E5-6")
      (libsource (lib "eagle-import") (part "CPOL-EUE5-6"))
    )
    (comp (ref "CN2")
      (value "3003-12")
      (footprint "eagle-import:3003-12")
      (libsource (lib "eagle-import") (part "3003-12"))
    )
    (comp (ref "D2")
      (value "1N4007")
      (footprint "eagle-import:SMA-DO214AC")
      (libsource (lib "eagle-import") (part "GF1"))
    )
    (comp (ref "IC1")
      (value "LM2596S-3V3")
      (footprint "eagle-import:TO263-5")
      (fields (field (name "MF") "NATIONAL SEMICONDUCTOR") (field (name "MPN") "LM2596S-ADJ/NOPB"))
      (libsource (lib "eagle-import") (part "LM2596S"))
    )
    (comp (ref "L2")
      (value "100uH")
      (footprint "eagle-import:DR127")
      (libsource (lib "eagle-import") (part "DR127"))
    )
    (comp (ref "U$13")
      (value "SK36_R1_00001")
      (footprint "eagle-import:SMC")
      (libsource (lib "eagle-import") (part "B540C_DIODE"))
    )
    (comp (ref "C13")
      (value "100nF")
      (footprint "eagle-import:C0603K")
      (libsource (lib "eagle-import") (part "C-EUC0603K"))
    )
    (comp (ref "C14")
      (value "100nF")
      (footprint "eagle-import:C0603K")
      (libsource (lib "eagle-import") (part "C-EUC0603K"))
    )
    (comp (ref "IC9")
      (value "MCP2551T-E/SN")
      (footprint "eagle-import:SOIC08")
      (libsource (lib "eagle-import") (part "MCP2551T-E/SN"))
    )
    (comp (ref "IC11")
      (value "MCP2551T-E/SN")
      (footprint "eagle-import:SOIC08")
      (libsource (lib "eagle-import") (part "MCP2551T-E/SN"))
    )
    (comp (ref "R76")
      (value "120R")
      (footprint "eagle-import:R0603")
      (libsource (lib "eagle-import") (part "R-EU_R0603"))
    )
    (comp (ref "R77")
      (value "120R")
      (footprint "eagle-import:R0603")
      (libsource (lib "eagle-import") (part "R-EU_R0603"))
    )
  )
  (nets
    (net (code "1") (name "+3V3") (class "Default")
      (node (ref "C10") (pin "1") (pinfunction "1_1") (pintype "passive"))
      (node (ref "C11") (pin "1") (pinfunction "1_1") (pintype "passive"))
      (node (ref "C12") (pin "1") (pinfunction "1_1") (pintype "passive"))
      (node (ref "C16") (pin "1") (pinfunction "1_1") (pintype "passive"))
      (node (ref "C17") (pin "1") (pinfunction "1_1") (pintype "passive"))
      (node (ref "C25") (pin "1") (pinfunction "1_1") (pintype "passive"))
      (node (ref "C26") (pin "1") (pinfunction "1_1") (pintype "passive"))
      (node (ref "C27") (pin "1") (pinfunction "1_1") (pintype "passive"))
      (node (ref "C28") (pin "1") (pinfunction "1_1") (pintype "passive"))
      (node (ref "C29") (pin "1") (pinfunction "1_1") (pintype "passive"))
      (node (ref "C30") (pin "1") (pinfunction "1_1") (pintype "passive"))
      (node (ref "C33") (pin "1") (pinfunction "1_1") (pintype "passive"))
      (node (ref "C34") (pin "1") (pinfunction "1_1") (pintype "passive"))
      (node (ref "C4") (pin "1") (pinfunction "1_1") (pintype "passive"))
      (node (ref "C40") (pin "+") (pinfunction "+_+") (pintype "passive"))
      (node (ref "C41") (pin "+") (pinfunction "+_+") (pintype "passive"))
      (node (ref "C42") (pin "+") (pinfunction "+_+") (pintype "passive"))
      (node (ref "C43") (pin "1") (pinfunction "1_1") (pintype "passive"))
      (node (ref "C5") (pin "+") (pinfunction "+_+") (pintype "passive"))
      (node (ref "C59") (pin "+") (pinfunction "+_+") (pintype "passive"))
      (node (ref "C6") (pin "1") (pinfunction "1_1") (pintype "passive"))
      (node (ref "C9") (pin "1") (pinfunction "1_1") (pintype "passive"))
      (node (ref "CN1") (pin "P$4") (pinfunction "VDD_P$4") (pintype "bidirectional"))
      (node (ref "IC1") (pin "4") (pinfunction "FB_4") (pintype "input"))
      (node (ref "IC14") (pin "8") (pinfunction "VCC_8") (pintype "power_in"))
      (node (ref "IC15") (pin "P$5") (pinfunction "IN_P$5") (pintype "bidirectional"))
      (node (ref "IC2") (pin "16") (pinfunction "VDD1_16") (pintype "bidirectional"))
      (node (ref "IC2") (pin "2") (pinfunction "VDD_2") (pintype "bidirectional"))
      (node (ref "IC2") (pin "30") (pinfunction "AVDD_30") (pintype "bidirectional"))
      (node (ref "IC2") (pin "37") (pinfunction "VDD2_37") (pintype "bidirectional"))
      (node (ref "IC2") (pin "46") (pinfunction "VDD3_46") (pintype "bidirectional"))
      (node (ref "IC2") (pin "55") (pinfunction "VUSB3V3_55") (pintype "bidirectional"))
      (node (ref "IC2") (pin "62") (pinfunction "VDD4_62") (pintype "bidirectional"))
      (node (ref "IC2") (pin "86") (pinfunction "VDD5_86") (pintype "bidirectional"))
      (node (ref "IC3") (pin "3") (pinfunction "A2*_3") (pintype "bidirectional"))
      (node (ref "IC3") (pin "8") (pinfunction "VCC_8") (pintype "bidirectional"))
      (node (ref "IC4") (pin "3") (pinfunction "A2*_3") (pintype "bidirectional"))
      (node (ref "IC4") (pin "8") (pinfunction "VCC_8") (pintype "bidirectional"))
      (node (ref "IC5") (pin "3") (pinfunction "A2*_3") (pintype "bidirectional"))
      (node (ref "IC5") (pin "8") (pinfunction "VCC_8") (pintype "bidirectional"))
      (node (ref "IC6") (pin "3") (pinfunction "A2*_3") (pintype "bidirectional"))
      (node (ref "IC6") (pin "8") (pinfunction "VCC_8") (pintype "bidirectional"))
      (node (ref "IC7") (pin "8") (pinfunction "VCC_8") (pintype "bidirectional"))
      (node (ref "IC8") (pin "8") (pinfunction "VCC_8") (pintype "bidirectional"))
      (node (ref "ICSP") (pin "2") (pinfunction "2_2") (pintype "passive"))
      (node (ref "L2") (pin "2") (pinfunction "2_2") (pintype "passive"))
      (node (ref "L3") (pin "1") (pinfunction "1_1") (pintype "passive"))
      (node (ref "LED1") (pin "A") (pinfunction "A_A") (pintype "passive"))
      (node (ref "LED2") (pin "A") (pinfunction "A_A") (pintype "passive"))
      (node (ref "LED3") (pin "A") (pinfunction "A_A") (pintype "passive"))
      (node (ref "LED4") (pin "A") (pinfunction "A_A") (pintype "passive"))
      (node (ref "LED5") (pin "A") (pinfunction "A_A") (pintype "passive"))
      (node (ref "LED6") (pin "A") (pinfunction "A_A") (pintype "passive"))
      (node (ref "LED7") (pin "A") (pinfunction "A_A") (pintype "passive"))
      (node (ref "OK11") (pin "1") (pinfunction "A_1") (pintype "passive"))
      (node (ref "OK14") (pin "1") (pinfunction "A_1") (pintype "passive"))
      (node (ref "R23") (pin "2") (pinfunction "2_2") (pintype "passive"))
      (node (ref "R41") (pin "2") (pinfunction "2_2") (pintype "passive"))
      (node (ref "R43") (pin "2") (pinfunction "2_2") (pintype "passive"))
      (node (ref "R46") (pin "2") (pinfunction "2_2") (pintype "passive"))
      (node (ref "R48") (pin "2") (pinfunction "2_2") (pintype "passive"))
      (node (ref "R49") (pin "2") (pinfunction "2_2") (pintype "passive"))
      (node (ref "R51") (pin "2") (pinfunction "2_2") (pintype "passive"))
      (node (ref "R55") (pin "2") (pinfunction "2_2") (pintype "passive"))
      (node (ref "R58") (pin "2") (pinfunction "2_2") (pintype "passive"))
      (node (ref "R60") (pin "2") (pinfunction "2_2") (pintype "passive"))
      (node (ref "R62") (pin "2") (pinfunction "2_2") (pintype "passive"))
      (node (ref "R74") (pin "2") (pinfunction "2_2") (pintype "passive"))
      (node (ref "R75") (pin "2") (pinfunction "2_2") (pintype "passive"))
      (node (ref "R78") (pin "2") (pinfunction "2_2") (pintype "passive"))
      (node (ref "R83") (pin "1") (pinfunction "1_1") (pintype "passive"))
      (node (ref "R84") (pin "2") (pinfunction "2_2") (pintype "passive"))
      (node (ref "R91") (pin "2") (pinfunction "2_2") (pintype "passive"))
      (node (ref "R96") (pin "2") (pinfunction "2_2") (pintype "passive"))
    )
    (net (code "2") (name "+12V") (class "Default")
      (node (ref "C1") (pin "1") (pinfunction "1_1") (pintype "passive"))
      (node (ref "C61") (pin "+") (pinfunction "+_+") (pintype "passive"))
      (node (ref "D2") (pin "K") (pinfunction "C_K") (pintype "passive"))
      (node (ref "IC1") (pin "1") (pinfunction "VIN_1") (pintype "input"))
      (node (ref "R21") (pin "2") (pinfunction "2_2") (pintype "passive"))
      (node (ref "R24") (pin "2") (pinfunction "2_2") (pintype "passive"))
      (node (ref "R35") (pin "2") (pinfunction "2_2") (pintype "passive"))
      (node (ref "R54") (pin "2") (pinfunction "2_2") (pintype "passive"))
      (node (ref "R7") (pin "2") (pinfunction "2_2") (pintype "passive"))
      (node (ref "R8") (pin "2") (pinfunction "2_2") (pintype "passive"))
    )
    (net (code "3") (name "0V") (class "Default")
      (node (ref "C1") (pin "2") (pinfunction "2_2") (pintype "passive"))
      (node (ref "C10") (pin "2") (pinfunction "2_2") (pintype "passive"))
      (node (ref "C11") (pin "2") (pinfunction "2_2") (pintype "passive"))
      (node (ref "C12") (pin "2") (pinfunction "2_2") (pintype "passive"))
      (node (ref "C13") (pin "1") (pinfunction "1_1") (pintype "passive"))
      (node (ref "C14") (pin "1") (pinfunction "1_1") (pintype "passive"))
      (node (ref "C15") (pin "2") (pinfunction "2_2") (pintype "passive"))
      (node (ref "C16") (pin "2") (pinfunction "2_2") (pintype "passive"))
      (node (ref "C17") (pin "2") (pinfunction "2_2") (pintype "passive"))
      (node (ref "C18") (pin "1") (pinfunction "1_1") (pintype "passive"))
      (node (ref "C2") (pin "2") (pinfunction "2_2") (pintype "passive"))
      (node (ref "C20") (pin "1") (pinfunction "1_1") (pintype "passive"))
      (node (ref "C23") (pin "1") (pinfunction "1_1") (pintype "passive"))
      (node (ref "C24") (pin "1") (pinfunction "1_1") (pintype "passive"))
      (node (ref "C25") (pin "2") (pinfunction "2_2") (pintype "passive"))
      (node (ref "C26") (pin "2") (pinfunction "2_2") (pintype "passive"))
      (node (ref "C27") (pin "2") (pinfunction "2_2") (pintype "passive"))
      (node (ref "C28") (pin "2") (pinfunction "2_2") (pintype "passive"))
      (node (ref "C29") (pin "2") (pinfunction "2_2") (pintype "passive"))
      (node (ref "C3") (pin "2") (pinfunction "2_2") (pintype "passive"))
      (node (ref "C30") (pin "2") (pinfunction "2_2") (pintype "passive"))
      (node (ref "C31") (pin "1") (pinfunction "1_1") (pintype "passive"))
      (node (ref "C32") (pin "1") (pinfunction "1_1") (pintype "passive"))
      (node (ref "C33") (pin "2") (pinfunction "2_2") (pintype "passive"))
      (node (ref "C34") (pin "2") (pinfunction "2_2") (pintype "passive"))
      (node (ref "C35") (pin "-") (pinfunction "-_-") (pintype "passive"))
      (node (ref "C36") (pin "2") (pinfunction "2_2") (pintype "passive"))
      (node (ref "C4") (pin "2") (pinfunction "2_2") (pintype "passive"))
      (node (ref "C40") (pin "-") (pinfunction "-_-") (pintype "passive"))
      (node (ref "C41") (pin "-") (pinfunction "-_-") (pintype "passive"))
      (node (ref "C42") (pin "-") (pinfunction "-_-") (pintype "passive"))
      (node (ref "C43") (pin "2") (pinfunction "2_2") (pintype "passive"))
      (node (ref "C45") (pin "2") (pinfunction "2_2") (pintype "passive"))
      (node (ref "C46") (pin "-") (pinfunction "-_-") (pintype "passive"))
      (node (ref "C48") (pin "-") (pinfunction "-_-") (pintype "passive"))
      (node (ref "C49") (pin "2") (pinfunction "2_2") (pintype "passive"))
      (node (ref "C5") (pin "-") (pinfunction "-_-") (pintype "passive"))
      (node (ref "C59") (pin "-") (pinfunction "-_-") (pintype "passive"))
      (node (ref "C6") (pin "2") (pinfunction "2_2") (pintype "passive"))
      (node (ref "C61") (pin "-") (pinfunction "-_-") (pintype "passive"))
      (node (ref "C63") (pin "-") (pinfunction "-_-") (pintype "passive"))
      (node (ref "C7") (pin "-") (pinfunction "-_-") (pintype "passive"))
      (node (ref "C8") (pin "2") (pinfunction "2_2") (pintype "passive"))
      (node (ref "C9") (pin "2") (pinfunction "2_2") (pintype "passive"))
      (node (ref "CN1") (pin "P$6") (pinfunction "VSS_P$6") (pintype "bidirectional"))
      (node (ref "CN2") (pin "P$1") (pinfunction "P$1_P$1") (pintype "bidirectional"))
      (node (ref "CN2") (pin "P$2") (pinfunction "P$2_P$2") (pintype "bidirectional"))
      (node (ref "CN2") (pin "P$23") (pinfunction "P$23_P$23") (pintype "bidirectional"))
      (node (ref "CN2") (pin "P$3") (pinfunction "P$3_P$3") (pintype "bidirectional"))
      (node (ref "CN2") (pin "P$4") (pinfunction "P$4_P$4") (pintype "bidirectional"))
      (node (ref "ETH2") (pin "P$10") (pinfunction "GND_P$10") (pintype "bidirectional"))
      (node (ref "IC1") (pin "3") (pinfunction "GND_3") (pintype "power_in"))
      (node (ref "IC1") (pin "5") (pinfunction "~{ON}/OFF_5") (pintype "input"))
      (node (ref "IC1") (pin "6") (pinfunction "6_6") (pintype "bidirectional"))
      (node (ref "IC10") (pin "5") (pinfunction "GND_5") (pintype "power_in"))
      (node (ref "IC11") (pin "2") (pinfunction "VSS_2") (pintype "bidirectional"))
      (node (ref "IC11") (pin "8") (pinfunction "RS_8") (pintype "bidirectional"))
      (node (ref "IC12") (pin "5") (pinfunction "GND_5") (pintype "power_in"))
      (node (ref "IC13") (pin "15") (pinfunction "GND_15") (pintype "power_in"))
      (node (ref "IC14") (pin "4") (pinfunction "GND_4") (pintype "power_in"))
      (node (ref "IC15") (pin "P$2") (pinfunction "GND_P$2") (pintype "bidirectional"))
      (node (ref "IC2") (pin "15") (pinfunction "VSS_15") (pintype "bidirectional"))
      (node (ref "IC2") (pin "31") (pinfunction "AVSS_31") (pintype "bidirectional"))
      (node (ref "IC2") (pin "36") (pinfunction "VSS1_36") (pintype "bidirectional"))
      (node (ref "IC2") (pin "45") (pinfunction "VSS2_45") (pintype "bidirectional"))
      (node (ref "IC2") (pin "65") (pinfunction "VSS3_65") (pintype "bidirectional"))
      (node (ref "IC2") (pin "75") (pinfunction "VSS4_75") (pintype "bidirectional"))
      (node (ref "IC3") (pin "4") (pinfunction "VSS_4") (pintype "bidirectional"))
      (node (ref "IC3") (pin "7") (pinfunction "WP_7") (pintype "bidirectional"))
      (node (ref "IC4") (pin "4") (pinfunction "VSS_4") (pintype "bidirectional"))
      (node (ref "IC4") (pin "7") (pinfunction "WP_7") (pintype "bidirectional"))
      (node (ref "IC5") (pin "4") (pinfunction "VSS_4") (pintype "bidirectional"))
      (node (ref "IC5") (pin "7") (pinfunction "WP_7") (pintype "bidirectional"))
      (node (ref "IC6") (pin "4") (pinfunction "VSS_4") (pintype "bidirectional"))
      (node (ref "IC6") (pin "7") (pinfunction "WP_7") (pintype "bidirectional"))
      (node (ref "IC7") (pin "4") (pinfunction "GND_4") (pintype "bidirectional"))
      (node (ref "IC7") (pin "7") (pinfunction "WP_7") (pintype "bidirectional"))
      (node (ref "IC8") (pin "4") (pinfunction "GND_4") (pintype "bidirectional"))
      (node (ref "IC8") (pin "7") (pinfunction "WP_7") (pintype "bidirectional"))
      (node (ref "IC9") (pin "8") (pinfunction "RS_8") (pintype "bidirectional"))
      (node (ref "ICSP") (pin "3") (pinfunction "3_3") (pintype "passive"))
      (node (ref "OK1") (pin "3") (pinfunction "EMIT_3") (pintype "passive"))
      (node (ref "OK2") (pin "3") (pinfunction "EMIT_3") (pintype "passive"))
      (node (ref "OK3") (pin "3") (pinfunction "EMIT_3") (pintype "passive"))
      (node (ref "OK4") (pin "3") (pinfunction "EMIT_3") (pintype "passive"))
      (node (ref "OK5") (pin "3") (pinfunction "EMIT_3") (pintype "passive"))
      (node (ref "OK6") (pin "3") (pinfunction "EMIT_3") (pintype "passive"))
      (node (ref "Q1") (pin "E") (pinfunction "E_E") (pintype "passive"))
      (node (ref "Q4") (pin "E") (pinfunction "E_E") (pintype "passive"))
      (node (ref "Q5") (pin "E") (pinfunction "E_E") (pintype "passive"))
      (node (ref "Q8") (pin "E") (pinfunction "E_E") (pintype "passive"))
      (node (ref "Q9") (pin "E") (pinfunction "E_E") (pintype "passive"))
      (node (ref "R38") (pin "2") (pinfunction "2_2") (pintype "passive"))
      (node (ref "R39") (pin "2") (pinfunction "2_2") (pintype "passive"))
      (node (ref "R42") (pin "2") (pinfunction "2_2") (pintype "passive"))
      (node (ref "R45") (pin "2") (pinfunction "2_2") (pintype "passive"))
      (node (ref "R47") (pin "2") (pinfunction "2_2") (pintype "passive"))
      (node (ref "R50") (pin "2") (pinfunction "2_2") (pintype "passive"))
      (node (ref "R52") (pin "2") (pinfunction "2_2") (pintype "passive"))
      (node (ref "R57") (pin "2") (pinfunction "2_2") (pintype "passive"))
      (node (ref "R59") (pin "2") (pinfunction "2_2") (pintype "passive"))
      (node (ref "R61") (pin "2") (pinfunction "2_2") (pintype "passive"))
      (node (ref "R63") (pin "2") (pinfunction "2_2") (pintype "passive"))
      (node (ref "R65") (pin "1") (pinfunction "1_1") (pintype "passive"))
      (node (ref "R66") (pin "2") (pinfunction "2_2") (pintype "passive"))
      (node (ref "R68") (pin "1") (pinfunction "1_1") (pintype "passive"))
      (node (ref "R81") (pin "2") (pinfunction "2_2") (pintype "passive"))
      (node (ref "R82") (pin "2") (pinfunction "2_2") (pintype "passive"))
      (node (ref "R86") (pin "1") (pinfunction "1_1") (pintype "passive"))
      (node (ref "R87") (pin "1") (pinfunction "1_1") (pintype "passive"))
      (node (ref "R88") (pin "2") (pinfunction "2_2") (pintype "passive"))
      (node (ref "R92") (pin "1") (pinfunction "1_1") (pintype "passive"))
      (node (ref "R95") (pin "2") (pinfunction "2_2") (pintype "passive"))
      (node (ref "SV1") (pin "3") (pinfunction "3_3") (pintype "passive"))
      (node (ref "U$1") (pin "3") (pinfunction "3_3") (pintype "bidirectional"))
      (node (ref "U$13") (pin "P$2") (pinfunction "P$2_P$2") (pintype "bidirectional"))
      (node (ref "U$3") (pin "3") (pinfunction "3_3") (pintype "bidirectional"))
      (node (ref "U$4") (pin "2") (pinfunction "P$1_2") (pintype "bidirectional"))
    )
    (net (code "4") (name "3V3_ETH") (class "Default")
      (node (ref "C49") (pin "1") (pinfunction "1_1") (pintype "passive"))
      (node (ref "C63") (pin "+") (pinfunction "+_+") (pintype "passive"))
      (node (ref "C7") (pin "+") (pinfunction "+_+") (pintype "passive"))
      (node (ref "C8") (pin "1") (pinfunction "1_1") (pintype "passive"))
      (node (ref "ETH2") (pin "P$11") (pinfunction "VCC_3V3_P$11") (pintype "bidirectional"))
      (node (ref "ETH2") (pin "P$14") (pinfunction "LED_3V3_1_P$14") (pintype "bidirectional"))
      (node (ref "ETH2") (pin "P$15") (pinfunction "LED_3V3_2_P$15") (pintype "bidirectional"))
      (node (ref "IC15") (pin "P$1") (pinfunction "OUT_P$1") (pintype "bidirectional"))
      (node (ref "R91") (pin "1") (pinfunction "1_1") (pintype "passive"))
    )
    (net (code "5") (name "A1") (class "Default")
      (node (ref "CN2") (pin "P$10") (pinfunction "P$10_P$10") (pintype "bidirectional"))
      (node (ref "IC10") (pin "6") (pinfunction "A_6") (pintype "output"))
      (node (ref "R53") (pin "2") (pinfunction "2_2") (pintype "passive"))
      (node (ref "R64") (pin "1") (pinfunction "1_1") (pintype "passive"))
      (node (ref "U$3") (pin "2") (pinfunction "2_2") (pintype "bidirectional"))
    )
    (net (code "6") (name "A2") (class "Default")
      (node (ref "CN2") (pin "P$12") (pinfunction "P$12_P$12") (pintype "bidirectional"))
      (node (ref "IC12") (pin "6") (pinfunction "A_6") (pintype "output"))
      (node (ref "R85") (pin "1") (pinfunction "1_1") (pintype "passive"))
      (node (ref "R90") (pin "2") (pinfunction "2_2") (pintype "passive"))
      (node (ref "U$1") (pin "2") (pinfunction "2_2") (pintype "bidirectional"))
    )
    (net (code "7") (name "B1") (class "Default")
      (node (ref "CN2") (pin "P$9") (pinfunction "P$9_P$9") (pintype "bidirectional"))
      (node (ref "IC10") (pin "7") (pinfunction "B_7") (pintype "output"))
      (node (ref "R53") (pin "1") (pinfunction "1_1") (pintype "passive"))
      (node (ref "R65") (pin "2") (pinfunction "2_2") (pintype "passive"))
      (node (ref "U$3") (pin "1") (pinfunction "1_1") (pintype "bidirectional"))
    )
    (net (code "8") (name "B2") (class "Default")
      (node (ref "CN2") (pin "P$11") (pinfunction "P$11_P$11") (pintype "bidirectional"))
      (node (ref "IC12") (pin "7") (pinfunction "B_7") (pintype "output"))
      (node (ref "R86") (pin "2") (pinfunction "2_2") (pintype "passive"))
      (node (ref "R90") (pin "1") (pinfunction "1_1") (pintype "passive"))
      (node (ref "U$1") (pin "1") (pinfunction "1_1") (pintype "bidirectional"))
    )
    (net (code "9") (name "C1RX") (class "Default")
      (node (ref "IC11") (pin "4") (pinfunction "RXD_4") (pintype "bidirectional"))
      (node (ref "IC2") (pin "87") (pinfunction "C1RX/ETXD1/PMD11/RF0_87") (pintype "bidirectional"))
    )
    (net (code "10") (name "C1TX") (class "Default")
      (node (ref "IC11") (pin "1") (pinfunction "TXD_1") (pintype "bidirectional"))
      (node (ref "IC2") (pin "88") (pinfunction "C1TX/ETXD0/PMD10/RF1_88") (pintype "bidirectional"))
    )
    (net (code "11") (name "C2RX") (class "Default")
      (node (ref "IC2") (pin "90") (pinfunction "C2RX(1)/PMD8/RG0_90") (pintype "bidirectional"))
      (node (ref "IC9") (pin "4") (pinfunction "RXD_4") (pintype "bidirectional"))
    )
    (net (code "12") (name "C2TX") (class "Default")
      (node (ref "IC2") (pin "89") (pinfunction "C2TX(1)/ETXERR/PMD9/RG1_89") (pintype "bidirectional"))
      (node (ref "IC9") (pin "1") (pinfunction "TXD_1") (pintype "bidirectional"))
    )
    (net (code "13") (name "CANH1") (class "Default")
      (node (ref "CN2") (pin "P$5") (pinfunction "P$5_P$5") (pintype "bidirectional"))
      (node (ref "IC9") (pin "7") (pinfunction "CANH_7") (pintype "bidirectional"))
      (node (ref "R76") (pin "1") (pinfunction "1_1") (pintype "passive"))
    )
    (net (code "14") (name "CANH2") (class "Default")
      (node (ref "CN2") (pin "P$7") (pinfunction "P$7_P$7") (pintype "bidirectional"))
      (node (ref "IC11") (pin "7") (pinfunction "CANH_7") (pintype "bidirectional"))
      (node (ref "R77") (pin "1") (pinfunction "1_1") (pintype "passive"))
    )
    (net (code "15") (name "CANL1") (class "Default")
      (node (ref "CN2") (pin "P$6") (pinfunction "P$6_P$6") (pintype "bidirectional"))
      (node (ref "IC9") (pin "6") (pinfunction "CANL_6") (pintype "bidirectional"))
      (node (ref "R76") (pin "2") (pinfunction "2_2") (pintype "passive"))
    )
    (net (code "16") (name "CANL2") (class "Default")
      (node (ref "CN2") (pin "P$8") (pinfunction "P$8_P$8") (pintype "bidirectional"))
      (node (ref "IC11") (pin "6") (pinfunction "CANL_6") (pintype "bidirectional"))
      (node (ref "R77") (pin "2") (pinfunction "2_2") (pintype "passive"))
    )
    (net (code "17") (name "DO1") (class "Default")
      (node (ref "CN2") (pin "P$21") (pinfunction "P$21_P$21") (pintype "bidirectional"))
      (node (ref "OK14") (pin "4") (pinfunction "COL_4") (pintype "passive"))
      (node (ref "R18") (pin "1") (pinfunction "1_1") (pintype "passive"))
    )
    (net (code "18") (name "DO1_MCU") (class "Default")
      (node (ref "IC2") (pin "77") (pinfunction "OC3/RD2_77") (pintype "bidirectional"))
      (node (ref "R22") (pin "2") (pinfunction "2_2") (pintype "passive"))
    )
    (net (code "19") (name "DO2") (class "Default")
      (node (ref "CN2") (pin "P$22") (pinfunction "P$22_P$22") (pintype "bidirectional"))
      (node (ref "OK11") (pin "4") (pinfunction "COL_4") (pintype "passive"))
      (node (ref "R37") (pin "1") (pinfunction "1_1") (pintype "passive"))
    )
    (net (code "20") (name "DO2_MCU") (class "Default")
      (node (ref "IC2") (pin "76") (pinfunction "OC2/RD1_76") (pintype "bidirectional"))
      (node (ref "R40") (pin "2") (pinfunction "2_2") (pintype "passive"))
    )
    (net (code "21") (name "ETH_ENABLE") (class "Default")
      (node (ref "IC15") (pin "P$4") (pinfunction "EN_P$4") (pintype "bidirectional"))
      (node (ref "IC2") (pin "100") (pinfunction "PMD4/RE4_100") (pintype "bidirectional"))
    )
    (net (code "22") (name "EX_IN1_UP") (class "Default")
      (node (ref "CN2") (pin "P$14") (pinfunction "P$14_P$14") (pintype "bidirectional"))
      (node (ref "R26") (pin "1") (pinfunction "1_1") (pintype "passive"))
      (node (ref "R27") (pin "1") (pinfunction "1_1") (pintype "passive"))
    )
    (net (code "23") (name "EX_IN2_UP") (class "Default")
      (node (ref "CN2") (pin "P$15") (pinfunction "P$15_P$15") (pintype "bidirectional"))
      (node (ref "R29") (pin "1") (pinfunction "1_1") (pintype "passive"))
      (node (ref "R30") (pin "1") (pinfunction "1_1") (pintype "passive"))
    )
    (net (code "24") (name "EX_IN3_UP") (class "Default")
      (node (ref "CN2") (pin "P$16") (pinfunction "P$16_P$16") (pintype "bidirectional"))
      (node (ref "R69") (pin "1") (pinfunction "1_1") (pintype "passive"))
      (node (ref "R70") (pin "1") (pinfunction "1_1") (pintype "passive"))
    )
    (net (code "25") (name "EX_IN4_UP") (class "Default")
      (node (ref "CN2") (pin "P$17") (pinfunction "P$17_P$17") (pintype "bidirectional"))
      (node (ref "R72") (pin "1") (pinfunction "1_1") (pintype "passive"))
      (node (ref "R73") (pin "1") (pinfunction "1_1") (pintype "passive"))
    )
    (net (code "26") (name "EX_IN5_UP") (class "Default")
      (node (ref "CN2") (pin "P$18") (pinfunction "P$18_P$18") (pintype "bidirectional"))
      (node (ref "R10") (pin "1") (pinfunction "1_1") (pintype "passive"))
      (node (ref "R12") (pin "1") (pinfunction "1_1") (pintype "passive"))
    )
    (net (code "27") (name "EX_IN6_UP") (class "Default")
      (node (ref "CN2") (pin "P$19") (pinfunction "P$19_P$19") (pintype "bidirectional"))
      (node (ref "R14") (pin "1") (pinfunction "1_1") (pintype "passive"))
      (node (ref "R16") (pin "1") (pinfunction "1_1") (pintype "passive"))
    )
    (net (code "28") (name "FILTERED_SUPPLY") (class "Default")
      (node (ref "C13") (pin "2") (pinfunction "2_2") (pintype "passive"))
      (node (ref "C14") (pin "2") (pinfunction "2_2") (pintype "passive"))
      (node (ref "C15") (pin "1") (pinfunction "1_1") (pintype "passive"))
      (node (ref "C2") (pin "1") (pinfunction "1_1") (pintype "passive"))
      (node (ref "C45") (pin "1") (pinfunction "1_1") (pintype "passive"))
      (node (ref "IC10") (pin "8") (pinfunction "VCC_8") (pintype "power_in"))
      (node (ref "IC11") (pin "3") (pinfunction "VDD_3") (pintype "bidirectional"))
      (node (ref "IC12") (pin "8") (pinfunction "VCC_8") (pintype "power_in"))
      (node (ref "IC13") (pin "16") (pinfunction "VCC_16") (pintype "power_in"))
      (node (ref "IC9") (pin "3") (pinfunction "VDD_3") (pintype "bidirectional"))
      (node (ref "L3") (pin "2") (pinfunction "2_2") (pintype "passive"))
      (node (ref "R64") (pin "2") (pinfunction "2_2") (pintype "passive"))
      (node (ref "R85") (pin "2") (pinfunction "2_2") (pintype "passive"))
    )
    (net (code "29") (name "GND1") (class "Default")
      (node (ref "CN2") (pin "P$20") (pinfunction "P$20_P$20") (pintype "bidirectional"))
      (node (ref "R20") (pin "2") (pinfunction "2_2") (pintype "passive"))
      (node (ref "R36") (pin "2") (pinfunction "2_2") (pintype "passive"))
      (node (ref "R68") (pin "2") (pinfunction "2_2") (pintype "passive"))
      (node (ref "T3") (pin "E") (pinfunction "E_E") (pintype "passive"))
      (node (ref "T6") (pin "E") (pinfunction "E_E") (pintype "passive"))
    )
    (net (code "30") (name "IN1") (class "Default")
      (node (ref "IC2") (pin "71") (pinfunction "EMDC/AEMDC/IC4/PMCS1/PMA14/RD11_71") (pintype "bidirectional"))
      (node (ref "OK2") (pin "4") (pinfunction "COL_4") (pintype "passive"))
      (node (ref "R19") (pin "1") (pinfunction "1_1") (pintype "passive"))
    )
    (net (code "31") (name "IN2") (class "Default")
      (node (ref "IC2") (pin "25") (pinfunction "PGED1/AN0/CN2/RB0_25") (pintype "bidirectional"))
      (node (ref "OK1") (pin "4") (pinfunction "COL_4") (pintype "passive"))
      (node (ref "R15") (pin "1") (pinfunction "1_1") (pintype "passive"))
    )
    (net (code "32") (name "IN3") (class "Default")
      (node (ref "IC2") (pin "24") (pinfunction "PGEC1/AN1/CN3/RB1_24") (pintype "bidirectional"))
      (node (ref "OK4") (pin "4") (pinfunction "COL_4") (pintype "passive"))
      (node (ref "R34") (pin "1") (pinfunction "1_1") (pintype "passive"))
    )
    (net (code "33") (name "IN4") (class "Default")
      (node (ref "IC2") (pin "23") (pinfunction "AN2/C2IN-/CN4/RB2_23") (pintype "bidirectional"))
      (node (ref "OK3") (pin "4") (pinfunction "COL_4") (pintype "passive"))
      (node (ref "R33") (pin "1") (pinfunction "1_1") (pintype "passive"))
    )
    (net (code "34") (name "IN5") (class "Default")
      (node (ref "IC2") (pin "22") (pinfunction "AN3/C2IN+/CN5/RB3_22") (pintype "bidirectional"))
      (node (ref "OK6") (pin "4") (pinfunction "COL_4") (pintype "passive"))
      (node (ref "R6") (pin "1") (pinfunction "1_1") (pintype "passive"))
    )
    (net (code "35") (name "IN6") (class "Default")
      (node (ref "IC2") (pin "21") (pinfunction "AN4/C1IN-/CN6/RB4_21") (pintype "bidirectional"))
      (node (ref "OK5") (pin "4") (pinfunction "COL_4") (pintype "passive"))
      (node (ref "R5") (pin "1") (pinfunction "1_1") (pintype "passive"))
    )
    (net (code "36") (name "MCLR") (class "Default")
      (node (ref "IC2") (pin "13") (pinfunction "MCLR_13") (pintype "bidirectional"))
      (node (ref "ICSP") (pin "1") (pinfunction "1_1") (pintype "passive"))
      (node (ref "R11") (pin "1") (pinfunction "1_1") (pintype "passive"))
    )
    (net (code "37") (name "MPF_OUT") (class "Default")
      (node (ref "IC14") (pin "7") (pinfunction "SQW/OUT_7") (pintype "output"))
      (node (ref "IC2") (pin "97") (pinfunction "TRD0/RG13_97") (pintype "bidirectional"))
      (node (ref "R96") (pin "1") (pinfunction "1_1") (pintype "passive"))
    )
    (net (code "38") (name "Net-(C3-Pad1)") (class "Default")
      (node (ref "C3") (pin "1") (pinfunction "1_1") (pintype "passive"))
      (node (ref "R11") (pin "2") (pinfunction "2_2") (pintype "passive"))
      (node (ref "R23") (pin "1") (pinfunction "1_1") (pintype "passive"))
    )
    (net (code "39") (name "Net-(ETH2-LED_DATA+)") (class "Default")
      (node (ref "ETH2") (pin "P$13") (pinfunction "LED_DATA-_P$13") (pintype "bidirectional"))
      (node (ref "ETH2") (pin "P$7") (pinfunction "LED_DATA+_P$7") (pintype "bidirectional"))
    )
    (net (code "40") (name "Net-(ETH2-LED_LINK+)") (class "Default")
      (node (ref "ETH2") (pin "P$12") (pinfunction "LED_LINK+_P$12") (pintype "bidirectional"))
      (node (ref "ETH2") (pin "P$16") (pinfunction "LED_LINK-_P$16") (pintype "bidirectional"))
    )
    (net (code "41") (name "Net-(IC1-OUT)") (class "Default")
      (node (ref "IC1") (pin "2") (pinfunction "OUT_2") (pintype "output"))
      (node (ref "L2") (pin "1") (pinfunction "1_1") (pintype "passive"))
      (node (ref "U$13") (pin "P$1") (pinfunction "P$1_P$1") (pintype "bidirectional"))
    )
    (net (code "42") (name "Net-(IC2-SOSCI{slash}CN1{slash}RC13)") (class "Default")
      (node (ref "C23") (pin "2") (pinfunction "2_2") (pintype "passive"))
      (node (ref "IC2") (pin "73") (pinfunction "SOSCI/CN1/RC13_73") (pintype "bidirectional"))
      (node (ref "Q2") (pin "2") (pinfunction "2_2") (pintype "passive"))
    )
    (net (code "43") (name "Net-(IC2-SOSCO{slash}T1CK{slash}CN0{slash}RC14)") (class "Default")
      (node (ref "C24") (pin "2") (pinfunction "2_2") (pintype "passive"))
      (node (ref "IC2") (pin "74") (pinfunction "SOSCO/T1CK/CN0/RC14_74") (pintype "bidirectional"))
      (node (ref "Q2") (pin "1") (pinfunction "1_1") (pintype "passive"))
    )
    (net (code "44") (name "Net-(IC2-VBUS)") (class "Default")
      (node (ref "IC2") (pin "54") (pinfunction "VBUS_54") (pintype "bidirectional"))
      (node (ref "R87") (pin "2") (pinfunction "2_2") (pintype "passive"))
    )
    (net (code "45") (name "Net-(IC3-A0)") (class "Default")
      (node (ref "IC3") (pin "1") (pinfunction "A0_1") (pintype "bidirectional"))
      (node (ref "R46") (pin "1") (pinfunction "1_1") (pintype "passive"))
      (node (ref "R47") (pin "1") (pinfunction "1_1") (pintype "passive"))
    )
    (net (code "46") (name "Net-(IC3-A1)") (class "Default")
      (node (ref "IC3") (pin "2") (pinfunction "A1_2") (pintype "bidirectional"))
      (node (ref "R49") (pin "1") (pinfunction "1_1") (pintype "passive"))
      (node (ref "R50") (pin "1") (pinfunction "1_1") (pintype "passive"))
    )
    (net (code "47") (name "Net-(IC4-A0)") (class "Default")
      (node (ref "IC4") (pin "1") (pinfunction "A0_1") (pintype "bidirectional"))
      (node (ref "R51") (pin "1") (pinfunction "1_1") (pintype "passive"))
      (node (ref "R52") (pin "1") (pinfunction "1_1") (pintype "passive"))
    )
    (net (code "48") (name "Net-(IC4-A1)") (class "Default")
      (node (ref "IC4") (pin "2") (pinfunction "A1_2") (pintype "bidirectional"))
      (node (ref "R55") (pin "1") (pinfunction "1_1") (pintype "passive"))
      (node (ref "R57") (pin "1") (pinfunction "1_1") (pintype "passive"))
    )
    (net (code "49") (name "Net-(IC5-A0)") (class "Default")
      (node (ref "IC5") (pin "1") (pinfunction "A0_1") (pintype "bidirectional"))
      (node (ref "R41") (pin "1") (pinfunction "1_1") (pintype "passive"))
      (node (ref "R42") (pin "1") (pinfunction "1_1") (pintype "passive"))
    )
    (net (code "50") (name "Net-(IC5-A1)") (class "Default")
      (node (ref "IC5") (pin "2") (pinfunction "A1_2") (pintype "bidirectional"))
      (node (ref "R43") (pin "1") (pinfunction "1_1") (pintype "passive"))
      (node (ref "R45") (pin "1") (pinfunction "1_1") (pintype "passive"))
    )
    (net (code "51") (name "Net-(IC6-A0)") (class "Default")
      (node (ref "IC6") (pin "1") (pinfunction "A0_1") (pintype "bidirectional"))
      (node (ref "R58") (pin "1") (pinfunction "1_1") (pintype "passive"))
      (node (ref "R59") (pin "1") (pinfunction "1_1") (pintype "passive"))
    )
    (net (code "52") (name "Net-(IC6-A1)") (class "Default")
      (node (ref "IC6") (pin "2") (pinfunction "A1_2") (pintype "bidirectional"))
      (node (ref "R60") (pin "1") (pinfunction "1_1") (pintype "passive"))
      (node (ref "R61") (pin "1") (pinfunction "1_1") (pintype "passive"))
    )
    (net (code "53") (name "Net-(IC7-A2)") (class "Default")
      (node (ref "IC7") (pin "3") (pinfunction "A2_3") (pintype "bidirectional"))
      (node (ref "R63") (pin "1") (pinfunction "1_1") (pintype "passive"))
    )
    (net (code "54") (name "Net-(IC8-A2)") (class "Default")
      (node (ref "IC8") (pin "3") (pinfunction "A2_3") (pintype "bidirectional"))
      (node (ref "R62") (pin "1") (pinfunction "1_1") (pintype "passive"))
    )
    (net (code "55") (name "Net-(IC10-D)") (class "Default")
      (node (ref "IC10") (pin "4") (pinfunction "D_4") (pintype "input"))
      (node (ref "R67") (pin "1") (pinfunction "1_1") (pintype "passive"))
    )
    (net (code "56") (name "Net-(IC10-R)") (class "Default")
      (node (ref "IC10") (pin "1") (pinfunction "R_1") (pintype "input"))
      (node (ref "R97") (pin "2") (pinfunction "2_2") (pintype "passive"))
    )
    (net (code "57") (name "Net-(IC12-D)") (class "Default")
      (node (ref "IC12") (pin "4") (pinfunction "D_4") (pintype "input"))
      (node (ref "R98") (pin "2") (pinfunction "2_2") (pintype "passive"))
    )
    (net (code "58") (name "Net-(IC12-R)") (class "Default")
      (node (ref "IC12") (pin "1") (pinfunction "R_1") (pintype "input"))
      (node (ref "R89") (pin "1") (pinfunction "1_1") (pintype "passive"))
    )
    (net (code "59") (name "Net-(IC13A-C1+)") (class "Default")
      (node (ref "C62") (pin "+") (pinfunction "+_+") (pintype "passive"))
      (node (ref "IC13") (pin "1") (pinfunction "C1+_1") (pintype "bidirectional"))
    )
    (net (code "60") (name "Net-(IC13A-C1-)") (class "Default")
      (node (ref "C62") (pin "-") (pinfunction "-_-") (pintype "passive"))
      (node (ref "IC13") (pin "3") (pinfunction "C1-_3") (pintype "bidirectional"))
    )
    (net (code "61") (name "Net-(IC13A-C2+)") (class "Default")
      (node (ref "C19") (pin "+") (pinfunction "+_+") (pintype "passive"))
      (node (ref "IC13") (pin "4") (pinfunction "C2+_4") (pintype "bidirectional"))
    )
    (net (code "62") (name "Net-(IC13A-C2-)") (class "Default")
      (node (ref "C19") (pin "-") (pinfunction "-_-") (pintype "passive"))
      (node (ref "IC13") (pin "5") (pinfunction "C2-_5") (pintype "bidirectional"))
    )
    (net (code "63") (name "Net-(IC13A-R2IN)") (class "Default")
      (node (ref "IC13") (pin "8") (pinfunction "R2IN_8") (pintype "input"))
      (node (ref "SV1") (pin "2") (pinfunction "2_2") (pintype "passive"))
    )
    (net (code "64") (name "Net-(IC13A-T2OUT)") (class "Default")
      (node (ref "IC13") (pin "7") (pinfunction "T2OUT_7") (pintype "output"))
      (node (ref "SV1") (pin "1") (pinfunction "1_1") (pintype "passive"))
    )
    (net (code "65") (name "Net-(IC13A-V+)") (class "Default")
      (node (ref "C46") (pin "+") (pinfunction "+_+") (pintype "passive"))
      (node (ref "IC13") (pin "2") (pinfunction "V+_2") (pintype "bidirectional"))
    )
    (net (code "66") (name "Net-(IC13A-V-)") (class "Default")
      (node (ref "C48") (pin "+") (pinfunction "+_+") (pintype "passive"))
      (node (ref "IC13") (pin "6") (pinfunction "V-_6") (pintype "bidirectional"))
    )
    (net (code "67") (name "Net-(IC14-VBAT)") (class "Default")
      (node (ref "IC14") (pin "3") (pinfunction "VBAT_3") (pintype "power_in"))
      (node (ref "U$4") (pin "1") (pinfunction "P$2_1") (pintype "bidirectional"))
      (node (ref "U$4") (pin "3") (pinfunction "P$2_3") (pintype "bidirectional"))
    )
    (net (code "68") (name "Net-(IC14-X1)") (class "Default")
      (node (ref "C18") (pin "2") (pinfunction "2_2") (pintype "passive"))
      (node (ref "IC14") (pin "1") (pinfunction "X1_1") (pintype "input"))
      (node (ref "Q7") (pin "2") (pinfunction "2_2") (pintype "passive"))
    )
    (net (code "69") (name "Net-(IC14-X2)") (class "Default")
      (node (ref "C20") (pin "2") (pinfunction "2_2") (pintype "passive"))
      (node (ref "IC14") (pin "2") (pinfunction "X2_2") (pintype "output"))
      (node (ref "Q7") (pin "1") (pinfunction "1_1") (pintype "passive"))
    )
    (net (code "70") (name "Net-(IC15-FLG)") (class "Default")
      (node (ref "IC15") (pin "P$3") (pinfunction "FLG_P$3") (pintype "bidirectional"))
      (node (ref "R48") (pin "1") (pinfunction "1_1") (pintype "passive"))
    )
    (net (code "71") (name "Net-(LED1-PadC)") (class "Default")
      (node (ref "LED1") (pin "C") (pinfunction "C_C") (pintype "passive"))
      (node (ref "R15") (pin "2") (pinfunction "2_2") (pintype "passive"))
    )
    (net (code "72") (name "Net-(LED2-PadC)") (class "Default")
      (node (ref "LED2") (pin "C") (pinfunction "C_C") (pintype "passive"))
      (node (ref "R34") (pin "2") (pinfunction "2_2") (pintype "passive"))
    )
    (net (code "73") (name "Net-(LED3-PadC)") (class "Default")
      (node (ref "LED3") (pin "C") (pinfunction "C_C") (pintype "passive"))
      (node (ref "R19") (pin "2") (pinfunction "2_2") (pintype "passive"))
    )
    (net (code "74") (name "Net-(LED4-PadC)") (class "Default")
      (node (ref "LED4") (pin "C") (pinfunction "C_C") (pintype "passive"))
      (node (ref "R33") (pin "2") (pinfunction "2_2") (pintype "passive"))
    )
    (net (code "75") (name "Net-(LED5-PadC)") (class "Default")
      (node (ref "LED5") (pin "C") (pinfunction "C_C") (pintype "passive"))
      (node (ref "R6") (pin "2") (pinfunction "2_2") (pintype "passive"))
    )
    (net (code "76") (name "Net-(LED6-PadC)") (class "Default")
      (node (ref "LED6") (pin "C") (pinfunction "C_C") (pintype "passive"))
      (node (ref "R5") (pin "2") (pinfunction "2_2") (pintype "passive"))
    )
    (net (code "77") (name "Net-(LED7-PadC)") (class "Default")
      (node (ref "LED7") (pin "C") (pinfunction "C_C") (pintype "passive"))
      (node (ref "R93") (pin "2") (pinfunction "2_2") (pintype "passive"))
    )
    (net (code "78") (name "Net-(OK1-A)") (class "Default")
      (node (ref "OK1") (pin "1") (pinfunction "A_1") (pintype "passive"))
      (node (ref "R3") (pin "2") (pinfunction "2_2") (pintype "passive"))
    )
    (net (code "79") (name "Net-(OK1-C)") (class "Default")
      (node (ref "OK1") (pin "2") (pinfunction "C_2") (pintype "passive"))
      (node (ref "R28") (pin "2") (pinfunction "2_2") (pintype "passive"))
      (node (ref "R29") (pin "2") (pinfunction "2_2") (pintype "passive"))
    )
    (net (code "80") (name "Net-(OK2-A)") (class "Default")
      (node (ref "OK2") (pin "1") (pinfunction "A_1") (pintype "passive"))
      (node (ref "R4") (pin "2") (pinfunction "2_2") (pintype "passive"))
    )
    (net (code "81") (name "Net-(OK2-C)") (class "Default")
      (node (ref "OK2") (pin "2") (pinfunction "C_2") (pintype "passive"))
      (node (ref "R25") (pin "2") (pinfunction "2_2") (pintype "passive"))
      (node (ref "R26") (pin "2") (pinfunction "2_2") (pintype "passive"))
    )
    (net (code "82") (name "Net-(OK3-A)") (class "Default")
      (node (ref "OK3") (pin "1") (pinfunction "A_1") (pintype "passive"))
      (node (ref "R31") (pin "2") (pinfunction "2_2") (pintype "passive"))
    )
    (net (code "83") (name "Net-(OK3-C)") (class "Default")
      (node (ref "OK3") (pin "2") (pinfunction "C_2") (pintype "passive"))
      (node (ref "R71") (pin "2") (pinfunction "2_2") (pintype "passive"))
      (node (ref "R72") (pin "2") (pinfunction "2_2") (pintype "passive"))
    )
    (net (code "84") (name "Net-(OK4-A)") (class "Default")
      (node (ref "OK4") (pin "1") (pinfunction "A_1") (pintype "passive"))
      (node (ref "R32") (pin "2") (pinfunction "2_2") (pintype "passive"))
    )
    (net (code "85") (name "Net-(OK4-C)") (class "Default")
      (node (ref "OK4") (pin "2") (pinfunction "C_2") (pintype "passive"))
      (node (ref "R56") (pin "2") (pinfunction "2_2") (pintype "passive"))
      (node (ref "R69") (pin "2") (pinfunction "2_2") (pintype "passive"))
    )
    (net (code "86") (name "Net-(OK5-A)") (class "Default")
      (node (ref "OK5") (pin "1") (pinfunction "A_1") (pintype "passive"))
      (node (ref "R1") (pin "2") (pinfunction "2_2") (pintype "passive"))
    )
    (net (code "87") (name "Net-(OK5-C)") (class "Default")
      (node (ref "OK5") (pin "2") (pinfunction "C_2") (pintype "passive"))
      (node (ref "R13") (pin "2") (pinfunction "2_2") (pintype "passive"))
      (node (ref "R14") (pin "2") (pinfunction "2_2") (pintype "passive"))
    )
    (net (code "88") (name "Net-(OK6-A)") (class "Default")
      (node (ref "OK6") (pin "1") (pinfunction "A_1") (pintype "passive"))
      (node (ref "R2") (pin "2") (pinfunction "2_2") (pintype "passive"))
    )
    (net (code "89") (name "Net-(OK6-C)") (class "Default")
      (node (ref "OK6") (pin "2") (pinfunction "C_2") (pintype "passive"))
      (node (ref "R10") (pin "2") (pinfunction "2_2") (pintype "passive"))
      (node (ref "R9") (pin "2") (pinfunction "2_2") (pintype "passive"))
    )
    (net (code "90") (name "Net-(OK11-C)") (class "Default")
      (node (ref "OK11") (pin "2") (pinfunction "C_2") (pintype "passive"))
      (node (ref "R17") (pin "1") (pinfunction "1_1") (pintype "passive"))
    )
    (net (code "91") (name "Net-(OK11-EMIT)") (class "Default")
      (node (ref "OK11") (pin "3") (pinfunction "EMIT_3") (pintype "passive"))
      (node (ref "R36") (pin "1") (pinfunction "1_1") (pintype "passive"))
      (node (ref "T3") (pin "B") (pinfunction "B_B") (pintype "passive"))
    )
    (net (code "92") (name "Net-(OK14-C)") (class "Default")
      (node (ref "OK14") (pin "2") (pinfunction "C_2") (pintype "passive"))
      (node (ref "R44") (pin "1") (pinfunction "1_1") (pintype "passive"))
    )
    (net (code "93") (name "Net-(OK14-EMIT)") (class "Default")
      (node (ref "OK14") (pin "3") (pinfunction "EMIT_3") (pintype "passive"))
      (node (ref "R20") (pin "1") (pinfunction "1_1") (pintype "passive"))
      (node (ref "T6") (pin "B") (pinfunction "B_B") (pintype "passive"))
    )
    (net (code "94") (name "Net-(Q1-PadB)") (class "Default")
      (node (ref "Q1") (pin "B") (pinfunction "B_B") (pintype "passive"))
      (node (ref "R22") (pin "1") (pinfunction "1_1") (pintype "passive"))
      (node (ref "R38") (pin "1") (pinfunction "1_1") (pintype "passive"))
    )
    (net (code "95") (name "Net-(Q1-PadC)") (class "Default")
      (node (ref "Q1") (pin "C") (pinfunction "C_C") (pintype "passive"))
      (node (ref "R44") (pin "2") (pinfunction "2_2") (pintype "passive"))
    )
    (net (code "96") (name "Net-(Q4-PadB)") (class "Default")
      (node (ref "Q4") (pin "B") (pinfunction "B_B") (pintype "passive"))
      (node (ref "R39") (pin "1") (pinfunction "1_1") (pintype "passive"))
      (node (ref "R40") (pin "1") (pinfunction "1_1") (pintype "passive"))
    )
    (net (code "97") (name "Net-(Q4-PadC)") (class "Default")
      (node (ref "Q4") (pin "C") (pinfunction "C_C") (pintype "passive"))
      (node (ref "R17") (pin "2") (pinfunction "2_2") (pintype "passive"))
    )
    (net (code "98") (name "Net-(Q5-PadB)") (class "Default")
      (node (ref "Q5") (pin "B") (pinfunction "B_B") (pintype "passive"))
      (node (ref "R94") (pin "1") (pinfunction "1_1") (pintype "passive"))
      (node (ref "R95") (pin "1") (pinfunction "1_1") (pintype "passive"))
    )
    (net (code "99") (name "Net-(Q5-PadC)") (class "Default")
      (node (ref "Q5") (pin "C") (pinfunction "C_C") (pintype "passive"))
      (node (ref "R93") (pin "1") (pinfunction "1_1") (pintype "passive"))
    )
    (net (code "100") (name "Net-(Q8-PadB)") (class "Default")
      (node (ref "Q8") (pin "B") (pinfunction "B_B") (pintype "passive"))
      (node (ref "R79") (pin "2") (pinfunction "2_2") (pintype "passive"))
      (node (ref "R82") (pin "1") (pinfunction "1_1") (pintype "passive"))
    )
    (net (code "101") (name "Net-(Q9-PadB)") (class "Default")
      (node (ref "Q9") (pin "B") (pinfunction "B_B") (pintype "passive"))
      (node (ref "R80") (pin "2") (pinfunction "2_2") (pintype "passive"))
      (node (ref "R81") (pin "1") (pinfunction "1_1") (pintype "passive"))
    )
    (net (code "102") (name "Net-(R1-Pad1)") (class "Default")
      (node (ref "R1") (pin "1") (pinfunction "1_1") (pintype "passive"))
      (node (ref "R16") (pin "2") (pinfunction "2_2") (pintype "passive"))
      (node (ref "R7") (pin "1") (pinfunction "1_1") (pintype "passive"))
    )
    (net (code "103") (name "Net-(R12-Pad2)") (class "Default")
      (node (ref "R12") (pin "2") (pinfunction "2_2") (pintype "passive"))
      (node (ref "R2") (pin "1") (pinfunction "1_1") (pintype "passive"))
      (node (ref "R8") (pin "1") (pinfunction "1_1") (pintype "passive"))
    )
    (net (code "104") (name "Net-(R18-Pad2)") (class "Default")
      (node (ref "R18") (pin "2") (pinfunction "2_2") (pintype "passive"))
      (node (ref "T6") (pin "C") (pinfunction "C_C") (pintype "passive"))
    )
    (net (code "105") (name "Net-(R21-Pad1)") (class "Default")
      (node (ref "R21") (pin "1") (pinfunction "1_1") (pintype "passive"))
      (node (ref "R3") (pin "1") (pinfunction "1_1") (pintype "passive"))
      (node (ref "R30") (pin "2") (pinfunction "2_2") (pintype "passive"))
    )
    (net (code "106") (name "Net-(R24-Pad1)") (class "Default")
      (node (ref "R24") (pin "1") (pinfunction "1_1") (pintype "passive"))
      (node (ref "R27") (pin "2") (pinfunction "2_2") (pintype "passive"))
      (node (ref "R4") (pin "1") (pinfunction "1_1") (pintype "passive"))
    )
    (net (code "107") (name "Net-(R31-Pad1)") (class "Default")
      (node (ref "R31") (pin "1") (pinfunction "1_1") (pintype "passive"))
      (node (ref "R35") (pin "1") (pinfunction "1_1") (pintype "passive"))
      (node (ref "R73") (pin "2") (pinfunction "2_2") (pintype "passive"))
    )
    (net (code "108") (name "Net-(R32-Pad1)") (class "Default")
      (node (ref "R32") (pin "1") (pinfunction "1_1") (pintype "passive"))
      (node (ref "R54") (pin "1") (pinfunction "1_1") (pintype "passive"))
      (node (ref "R70") (pin "2") (pinfunction "2_2") (pintype "passive"))
    )
    (net (code "109") (name "Net-(R37-Pad2)") (class "Default")
      (node (ref "R37") (pin "2") (pinfunction "2_2") (pintype "passive"))
      (node (ref "T3") (pin "C") (pinfunction "C_C") (pintype "passive"))
    )
    (net (code "110") (name "OSC1") (class "Default")
      (node (ref "C31") (pin "2") (pinfunction "2_2") (pintype "passive"))
      (node (ref "IC2") (pin "63") (pinfunction "OSC1/CLKI/RC12_63") (pintype "bidirectional"))
      (node (ref "Q3") (pin "1") (pinfunction "1_1") (pintype "passive"))
    )
    (net (code "111") (name "OSC2") (class "Default")
      (node (ref "C32") (pin "2") (pinfunction "2_2") (pintype "passive"))
      (node (ref "IC2") (pin "64") (pinfunction "OSC2/CLKO/RC15_64") (pintype "bidirectional"))
      (node (ref "Q3") (pin "2") (pinfunction "2_2") (pintype "passive"))
    )
    (net (code "112") (name "PGC") (class "Default")
      (node (ref "IC2") (pin "26") (pinfunction "PGEC2/AN6/OCFA/RB6_26") (pintype "bidirectional"))
      (node (ref "ICSP") (pin "5") (pinfunction "5_5") (pintype "passive"))
    )
    (net (code "113") (name "PGD") (class "Default")
      (node (ref "IC2") (pin "27") (pinfunction "PGED2/AN7/RB7_27") (pintype "bidirectional"))
      (node (ref "ICSP") (pin "4") (pinfunction "4_4") (pintype "passive"))
    )
    (net (code "114") (name "RELOAD") (class "Default")
      (node (ref "ETH2") (pin "P$6") (pinfunction "RELOAD(CFG)_P$6") (pintype "bidirectional"))
      (node (ref "Q8") (pin "C") (pinfunction "C_C") (pintype "passive"))
    )
    (net (code "115") (name "RELOAD_UP_IO") (class "Default")
      (node (ref "IC2") (pin "99") (pinfunction "PMD3/RE3_99") (pintype "bidirectional"))
      (node (ref "R79") (pin "1") (pinfunction "1_1") (pintype "passive"))
    )
    (net (code "116") (name "RS485_CNTRL_2") (class "Default")
      (node (ref "IC12") (pin "2") (pinfunction "~{RE}_2") (pintype "input"))
      (node (ref "IC12") (pin "3") (pinfunction "DE_3") (pintype "input"))
      (node (ref "IC2") (pin "51") (pinfunction "USBID/RF3_51") (pintype "bidirectional"))
      (node (ref "R88") (pin "1") (pinfunction "1_1") (pintype "passive"))
    )
    (net (code "117") (name "RST") (class "Default")
      (node (ref "ETH2") (pin "P$4") (pinfunction "RST_P$4") (pintype "bidirectional"))
      (node (ref "Q9") (pin "C") (pinfunction "C_C") (pintype "passive"))
    )
    (net (code "118") (name "RST_UP_IO") (class "Default")
      (node (ref "IC2") (pin "98") (pinfunction "PMD2/RE2_98") (pintype "bidirectional"))
      (node (ref "R80") (pin "1") (pinfunction "1_1") (pintype "passive"))
    )
    (net (code "119") (name "RS_CNTRL") (class "Default")
      (node (ref "IC10") (pin "2") (pinfunction "~{RE}_2") (pintype "input"))
      (node (ref "IC10") (pin "3") (pinfunction "DE_3") (pintype "input"))
      (node (ref "IC2") (pin "38") (pinfunction "TCK/RA1_38") (pintype "bidirectional"))
      (node (ref "R66") (pin "1") (pinfunction "1_1") (pintype "passive"))
    )
    (net (code "120") (name "RX_ETH") (class "Default")
      (node (ref "ETH2") (pin "P$8") (pinfunction "RXD_P$8") (pintype "bidirectional"))
      (node (ref "IC2") (pin "53") (pinfunction "SCL3/SDO3/U1TX/RF8_53") (pintype "bidirectional"))
      (node (ref "R78") (pin "1") (pinfunction "1_1") (pintype "passive"))
    )
    (net (code "121") (name "SCK2") (class "Default")
      (node (ref "CN1") (pin "P$5") (pinfunction "CLK_P$5") (pintype "bidirectional"))
      (node (ref "IC2") (pin "10") (pinfunction "ECOL/SCK2/U6TX/U3RTS/PMA5/CN8/RG6_10") (pintype "bidirectional"))
    )
    (net (code "122") (name "SCL2") (class "Default")
      (node (ref "IC14") (pin "6") (pinfunction "SCL_6") (pintype "input"))
      (node (ref "IC2") (pin "58") (pinfunction "SCL2/RA2_58") (pintype "bidirectional"))
      (node (ref "IC3") (pin "6") (pinfunction "SCL_6") (pintype "bidirectional"))
      (node (ref "IC4") (pin "6") (pinfunction "SCL_6") (pintype "bidirectional"))
      (node (ref "IC5") (pin "6") (pinfunction "SCL_6") (pintype "bidirectional"))
      (node (ref "IC6") (pin "6") (pinfunction "SCL_6") (pintype "bidirectional"))
      (node (ref "IC7") (pin "6") (pinfunction "SCL_6") (pintype "bidirectional"))
      (node (ref "IC8") (pin "6") (pinfunction "SCL_6") (pintype "bidirectional"))
      (node (ref "R74") (pin "1") (pinfunction "1_1") (pintype "passive"))
    )
    (net (code "123") (name "SDA2") (class "Default")
      (node (ref "IC14") (pin "5") (pinfunction "SDA_5") (pintype "bidirectional"))
      (node (ref "IC2") (pin "59") (pinfunction "SDA2/RA3_59") (pintype "bidirectional"))
      (node (ref "IC3") (pin "5") (pinfunction "SDA_5") (pintype "bidirectional"))
      (node (ref "IC4") (pin "5") (pinfunction "SDA_5") (pintype "bidirectional"))
      (node (ref "IC5") (pin "5") (pinfunction "SDA_5") (pintype "bidirectional"))
      (node (ref "IC6") (pin "5") (pinfunction "SDA_5") (pintype "bidirectional"))
      (node (ref "IC7") (pin "5") (pinfunction "SDA_5") (pintype "bidirectional"))
      (node (ref "IC8") (pin "5") (pinfunction "SDA_5") (pintype "bidirectional"))
      (node (ref "R75") (pin "1") (pinfunction "1_1") (pintype "passive"))
    )
    (net (code "124") (name "SDI2") (class "Default")
      (node (ref "CN1") (pin "P$7") (pinfunction "DAT0_P$7") (pintype "bidirectional"))
      (node (ref "IC2") (pin "11") (pinfunction "ECRS/SDA4/SDI2/U3RX/PMA4/CN9/RG7_11") (pintype "bidirectional"))
    )
    (net (code "125") (name "SDO2") (class "Default")
      (node (ref "CN1") (pin "P$3") (pinfunction "CMD_P$3") (pintype "bidirectional"))
      (node (ref "IC2") (pin "12") (pinfunction "ERXDV/AERXDV/ECRSDV/AECRSDV/SCL4/SDO2/U3TX/PMA3/CN10/RG8_12") (pintype "bidirectional"))
    )
    (net (code "126") (name "SS2") (class "Default")
      (node (ref "CN1") (pin "P$2") (pinfunction "CD/DAT3_P$2") (pintype "bidirectional"))
      (node (ref "IC2") (pin "14") (pinfunction "ERXCLK/AERXCLK/EREFCLK/AEREFCLK/SS2/U6RX/U3CTS/PMA2/CN11/RG9_14") (pintype "bidirectional"))
      (node (ref "R84") (pin "1") (pinfunction "1_1") (pintype "passive"))
    )
    (net (code "127") (name "STATUS") (class "Default")
      (node (ref "IC2") (pin "95") (pinfunction "TRD2/RG14_95") (pintype "bidirectional"))
      (node (ref "R94") (pin "2") (pinfunction "2_2") (pintype "passive"))
    )
    (net (code "128") (name "TX_ETH") (class "Default")
      (node (ref "ETH2") (pin "P$9") (pinfunction "TXD_P$9") (pintype "bidirectional"))
      (node (ref "IC2") (pin "52") (pinfunction "SDA3/SDI3/U1RX/RF2_52") (pintype "bidirectional"))
      (node (ref "R83") (pin "2") (pinfunction "2_2") (pintype "passive"))
    )
    (net (code "129") (name "U2RX") (class "Default")
      (node (ref "IC2") (pin "49") (pinfunction "SDA5/SDI4/U2RX/PMA9/CN17/RF4_49") (pintype "bidirectional"))
      (node (ref "R89") (pin "2") (pinfunction "2_2") (pintype "passive"))
    )
    (net (code "130") (name "U2TX") (class "Default")
      (node (ref "IC2") (pin "50") (pinfunction "SCL5/SDO4/U2TX/PMA8/CN18/RF5_50") (pintype "bidirectional"))
      (node (ref "R98") (pin "1") (pinfunction "1_1") (pintype "passive"))
    )
    (net (code "131") (name "U4RX") (class "Default")
      (node (ref "IC13") (pin "9") (pinfunction "R2OUT_9") (pintype "output"))
      (node (ref "IC2") (pin "47") (pinfunction "AETXD0/SS3/U4RX/U1CTS/CN20/RD14_47") (pintype "bidirectional"))
    )
    (net (code "132") (name "U4TX") (class "Default")
      (node (ref "IC13") (pin "10") (pinfunction "T2IN_10") (pintype "input"))
      (node (ref "IC2") (pin "48") (pinfunction "AETXD1/SCK3/U4TX/U1RTS/CN21/RD15_48") (pintype "bidirectional"))
    )
    (net (code "133") (name "U5RX") (class "Default")
      (node (ref "IC2") (pin "40") (pinfunction "AC1RX/SS4/U5RX/U2CTS/RF12_40") (pintype "bidirectional"))
      (node (ref "R97") (pin "1") (pinfunction "1_1") (pintype "passive"))
    )
    (net (code "134") (name "U5TX") (class "Default")
      (node (ref "IC2") (pin "39") (pinfunction "AC1TX/SCK4/U5TX/U2RTS/RF13_39") (pintype "bidirectional"))
      (node (ref "R67") (pin "2") (pinfunction "2_2") (pintype "passive"))
    )
    (net (code "135") (name "VCAP") (class "Default")
      (node (ref "C35") (pin "+") (pinfunction "+_+") (pintype "passive"))
      (node (ref "C36") (pin "1") (pinfunction "1_1") (pintype "passive"))
      (node (ref "IC2") (pin "85") (pinfunction "VCAP/VDDCORE_85") (pintype "bidirectional"))
    )
    (net (code "136") (name "VIN") (class "Default")
      (node (ref "CN2") (pin "P$24") (pinfunction "P$24_P$24") (pintype "bidirectional"))
      (node (ref "D2") (pin "A") (pinfunction "A_A") (pintype "passive"))
    )
    (net (code "137") (name "VSS") (class "Default")
      (node (ref "CN2") (pin "P$13") (pinfunction "P$13_P$13") (pintype "bidirectional"))
      (node (ref "R13") (pin "1") (pinfunction "1_1") (pintype "passive"))
      (node (ref "R25") (pin "1") (pinfunction "1_1") (pintype "passive"))
      (node (ref "R28") (pin "1") (pinfunction "1_1") (pintype "passive"))
      (node (ref "R56") (pin "1") (pinfunction "1_1") (pintype "passive"))
      (node (ref "R71") (pin "1") (pinfunction "1_1") (pintype "passive"))
      (node (ref "R9") (pin "1") (pinfunction "1_1") (pintype "passive"))
      (node (ref "R92") (pin "2") (pinfunction "2_2") (pintype "passive"))
    )
    (net (code "138") (name "unconnected-(CN1-DAT1-PadP$8)") (class "Default")
      (node (ref "CN1") (pin "P$8") (pinfunction "DAT1_P$8") (pintype "bidirectional"))
    )
    (net (code "139") (name "unconnected-(CN1-DAT2-PadP$1)") (class "Default")
      (node (ref "CN1") (pin "P$1") (pinfunction "DAT2_P$1") (pintype "bidirectional"))
    )
    (net (code "140") (name "unconnected-(ETH2-LINK-PadP$3)") (class "Default")
      (node (ref "ETH2") (pin "P$3") (pinfunction "LINK_P$3") (pintype "bidirectional"))
    )
    (net (code "141") (name "unconnected-(ETH2-NC1-PadP$1)") (class "Default")
      (node (ref "ETH2") (pin "P$1") (pinfunction "NC1_P$1") (pintype "bidirectional"))
    )
    (net (code "142") (name "unconnected-(ETH2-NC2-PadP$2)") (class "Default")
      (node (ref "ETH2") (pin "P$2") (pinfunction "NC2_P$2") (pintype "bidirectional"))
    )
    (net (code "143") (name "unconnected-(ETH2-RTS-PadP$5)") (class "Default")
      (node (ref "ETH2") (pin "P$5") (pinfunction "RTS_P$5") (pintype "bidirectional"))
    )
    (net (code "144") (name "unconnected-(IC2-AERXD0{slash}INT1{slash}RE8-Pad18)") (class "Default")
      (node (ref "IC2") (pin "18") (pinfunction "AERXD0/INT1/RE8_18") (pintype "bidirectional"))
    )
    (net (code "145") (name "unconnected-(IC2-AERXD1{slash}INT2{slash}RE9-Pad19)") (class "Default")
      (node (ref "IC2") (pin "19") (pinfunction "AERXD1/INT2/RE9_19") (pintype "bidirectional"))
    )
    (net (code "146") (name "unconnected-(IC2-AERXERR{slash}RG15-Pad1)") (class "Default")
      (node (ref "IC2") (pin "1") (pinfunction "AERXERR/RG15_1") (pintype "bidirectional"))
    )
    (net (code "147") (name "unconnected-(IC2-AETXCLK{slash}SCL1{slash}INT3{slash}RA14-Pad66)") (class "Default")
      (node (ref "IC2") (pin "66") (pinfunction "AETXCLK/SCL1/INT3/RA14_66") (pintype "bidirectional"))
    )
    (net (code "148") (name "unconnected-(IC2-AETXEN{slash}SDA1{slash}INT4{slash}RA15-Pad67)") (class "Default")
      (node (ref "IC2") (pin "67") (pinfunction "AETXEN/SDA1/INT4/RA15_67") (pintype "bidirectional"))
    )
    (net (code "149") (name "unconnected-(IC2-AN5{slash}C1IN+{slash}VBUSON{slash}CN7{slash}RB5-Pad20)") (class "Default")
      (node (ref "IC2") (pin "20") (pinfunction "AN5/C1IN+/VBUSON/CN7/RB5_20") (pintype "bidirectional"))
    )
    (net (code "150") (name "unconnected-(IC2-AN8{slash}C1OUT{slash}RB8-Pad32)") (class "Default")
      (node (ref "IC2") (pin "32") (pinfunction "AN8/C1OUT/RB8_32") (pintype "bidirectional"))
    )
    (net (code "151") (name "unconnected-(IC2-AN9{slash}C2OUT{slash}RB9-Pad33)") (class "Default")
      (node (ref "IC2") (pin "33") (pinfunction "AN9/C2OUT/RB9_33") (pintype "bidirectional"))
    )
    (net (code "152") (name "unconnected-(IC2-AN10{slash}CVREFOUT{slash}PMA13{slash}RB10-Pad34)") (class "Default")
      (node (ref "IC2") (pin "34") (pinfunction "AN10/CVREFOUT/PMA13/RB10_34") (pintype "bidirectional"))
    )
    (net (code "153") (name "unconnected-(IC2-AN11{slash}ERXERR{slash}AETXERR{slash}PMA12{slash}RB11-Pad35)") (class "Default")
      (node (ref "IC2") (pin "35") (pinfunction "AN11/ERXERR/AETXERR/PMA12/RB11_35") (pintype "bidirectional"))
    )
    (net (code "154") (name "unconnected-(IC2-AN12{slash}ERXD0{slash}AECRS{slash}PMA11{slash}RB12-Pad41)") (class "Default")
      (node (ref "IC2") (pin "41") (pinfunction "AN12/ERXD0/AECRS/PMA11/RB12_41") (pintype "bidirectional"))
    )
    (net (code "155") (name "unconnected-(IC2-AN13{slash}ERXD1{slash}AECOL{slash}PMA10{slash}RB13-Pad42)") (class "Default")
      (node (ref "IC2") (pin "42") (pinfunction "AN13/ERXD1/AECOL/PMA10/RB13_42") (pintype "bidirectional"))
    )
    (net (code "156") (name "unconnected-(IC2-AN14{slash}ERXD2{slash}AETXD3{slash}PMALH{slash}PMA1{slash}RB14-Pad43)") (class "Default")
      (node (ref "IC2") (pin "43") (pinfunction "AN14/ERXD2/AETXD3/PMALH/PMA1/RB14_43") (pintype "bidirectional"))
    )
    (net (code "157") (name "unconnected-(IC2-AN15{slash}ERXD3{slash}AETXD2{slash}OCFB{slash}PMALL{slash}PMA0{slash}CN12{slash}RB15-Pad44)") (class "Default")
      (node (ref "IC2") (pin "44") (pinfunction "AN15/ERXD3/AETXD2/OCFB/PMALL/PMA0/CN12/RB15_44") (pintype "bidirectional"))
    )
    (net (code "158") (name "unconnected-(IC2-D+{slash}RG2-Pad57)") (class "Default")
      (node (ref "IC2") (pin "57") (pinfunction "D+/RG2_57") (pintype "bidirectional"))
    )
    (net (code "159") (name "unconnected-(IC2-D-{slash}RG3-Pad56)") (class "Default")
      (node (ref "IC2") (pin "56") (pinfunction "D-/RG3_56") (pintype "bidirectional"))
    )
    (net (code "160") (name "unconnected-(IC2-ETXCLK{slash}PMD15{slash}CN16{slash}RD7-Pad84)") (class "Default")
      (node (ref "IC2") (pin "84") (pinfunction "ETXCLK/PMD15/CN16/RD7_84") (pintype "bidirectional"))
    )
    (net (code "161") (name "unconnected-(IC2-ETXD2{slash}IC5{slash}PMD12{slash}RD12-Pad79)") (class "Default")
      (node (ref "IC2") (pin "79") (pinfunction "ETXD2/IC5/PMD12/RD12_79") (pintype "bidirectional"))
    )
    (net (code "162") (name "unconnected-(IC2-ETXD3{slash}PMD13{slash}CN19{slash}RD13-Pad80)") (class "Default")
      (node (ref "IC2") (pin "80") (pinfunction "ETXD3/PMD13/CN19/RD13_80") (pintype "bidirectional"))
    )
    (net (code "163") (name "unconnected-(IC2-ETXEN{slash}PMD14{slash}CN15{slash}RD6-Pad83)") (class "Default")
      (node (ref "IC2") (pin "83") (pinfunction "ETXEN/PMD14/CN15/RD6_83") (pintype "bidirectional"))
    )
    (net (code "164") (name "unconnected-(IC2-OC4{slash}RD3-Pad78)") (class "Default")
      (node (ref "IC2") (pin "78") (pinfunction "OC4/RD3_78") (pintype "bidirectional"))
    )
    (net (code "165") (name "unconnected-(IC2-OC5{slash}PMWR{slash}CN13{slash}RD4-Pad81)") (class "Default")
      (node (ref "IC2") (pin "81") (pinfunction "OC5/PMWR/CN13/RD4_81") (pintype "bidirectional"))
    )
    (net (code "166") (name "unconnected-(IC2-PMD0{slash}RE0-Pad93)") (class "Default")
      (node (ref "IC2") (pin "93") (pinfunction "PMD0/RE0_93") (pintype "bidirectional"))
    )
    (net (code "167") (name "unconnected-(IC2-PMD1{slash}RE1-Pad94)") (class "Default")
      (node (ref "IC2") (pin "94") (pinfunction "PMD1/RE1_94") (pintype "bidirectional"))
    )
    (net (code "168") (name "unconnected-(IC2-PMD5{slash}RE5-Pad3)") (class "Default")
      (node (ref "IC2") (pin "3") (pinfunction "PMD5/RE5_3") (pintype "bidirectional"))
    )
    (net (code "169") (name "unconnected-(IC2-PMD6{slash}RE6-Pad4)") (class "Default")
      (node (ref "IC2") (pin "4") (pinfunction "PMD6/RE6_4") (pintype "bidirectional"))
    )
    (net (code "170") (name "unconnected-(IC2-PMD7{slash}RE7-Pad5)") (class "Default")
      (node (ref "IC2") (pin "5") (pinfunction "PMD7/RE7_5") (pintype "bidirectional"))
    )
    (net (code "171") (name "unconnected-(IC2-PMRD{slash}CN14{slash}RD5-Pad82)") (class "Default")
      (node (ref "IC2") (pin "82") (pinfunction "PMRD/CN14/RD5_82") (pintype "bidirectional"))
    )
    (net (code "172") (name "unconnected-(IC2-RTCC{slash}EMDIO{slash}AEMDIO{slash}IC1{slash}RD8-Pad68)") (class "Default")
      (node (ref "IC2") (pin "68") (pinfunction "RTCC/EMDIO/AEMDIO/IC1/RD8_68") (pintype "bidirectional"))
    )
    (net (code "173") (name "unconnected-(IC2-SCK1{slash}IC3{slash}PMCS2{slash}PMA15{slash}RD10-Pad70)") (class "Default")
      (node (ref "IC2") (pin "70") (pinfunction "SCK1/IC3/PMCS2/PMA15/RD10_70") (pintype "bidirectional"))
    )
    (net (code "174") (name "unconnected-(IC2-SDO1{slash}OC1{slash}INT0{slash}RD0-Pad72)") (class "Default")
      (node (ref "IC2") (pin "72") (pinfunction "SDO1/OC1/INT0/RD0_72") (pintype "bidirectional"))
    )
    (net (code "175") (name "unconnected-(IC2-SS1{slash}IC2{slash}RD9-Pad69)") (class "Default")
      (node (ref "IC2") (pin "69") (pinfunction "SS1/IC2/RD9_69") (pintype "bidirectional"))
    )
    (net (code "176") (name "unconnected-(IC2-T2CK{slash}RC1-Pad6)") (class "Default")
      (node (ref "IC2") (pin "6") (pinfunction "T2CK/RC1_6") (pintype "bidirectional"))
    )
    (net (code "177") (name "unconnected-(IC2-T3CK{slash}AC2TX(1){slash}RC2-Pad7)") (class "Default")
      (node (ref "IC2") (pin "7") (pinfunction "T3CK/AC2TX(1)/RC2_7") (pintype "bidirectional"))
    )
    (net (code "178") (name "unconnected-(IC2-T4CK{slash}AC2RX(1){slash}RC3-Pad8)") (class "Default")
      (node (ref "IC2") (pin "8") (pinfunction "T4CK/AC2RX(1)/RC3_8") (pintype "bidirectional"))
    )
    (net (code "179") (name "unconnected-(IC2-T5CK{slash}SDI1{slash}RC4-Pad9)") (class "Default")
      (node (ref "IC2") (pin "9") (pinfunction "T5CK/SDI1/RC4_9") (pintype "bidirectional"))
    )
    (net (code "180") (name "unconnected-(IC2-TDI{slash}RA4-Pad60)") (class "Default")
      (node (ref "IC2") (pin "60") (pinfunction "TDI/RA4_60") (pintype "bidirectional"))
    )
    (net (code "181") (name "unconnected-(IC2-TDO{slash}RA5-Pad61)") (class "Default")
      (node (ref "IC2") (pin "61") (pinfunction "TDO/RA5_61") (pintype "bidirectional"))
    )
    (net (code "182") (name "unconnected-(IC2-TMS{slash}RA0-Pad17)") (class "Default")
      (node (ref "IC2") (pin "17") (pinfunction "TMS/RA0_17") (pintype "bidirectional"))
    )
    (net (code "183") (name "unconnected-(IC2-TRCLK{slash}RA6-Pad91)") (class "Default")
      (node (ref "IC2") (pin "91") (pinfunction "TRCLK/RA6_91") (pintype "bidirectional"))
    )
    (net (code "184") (name "unconnected-(IC2-TRD1{slash}RG12-Pad96)") (class "Default")
      (node (ref "IC2") (pin "96") (pinfunction "TRD1/RG12_96") (pintype "bidirectional"))
    )
    (net (code "185") (name "unconnected-(IC2-TRD3{slash}RA7-Pad92)") (class "Default")
      (node (ref "IC2") (pin "92") (pinfunction "TRD3/RA7_92") (pintype "bidirectional"))
    )
    (net (code "186") (name "unconnected-(IC2-VREF+{slash}CVREF+{slash}AERXD3{slash}PMA6{slash}RA10-Pad29)") (class "Default")
      (node (ref "IC2") (pin "29") (pinfunction "VREF+/CVREF+/AERXD3/PMA6/RA10_29") (pintype "bidirectional"))
    )
    (net (code "187") (name "unconnected-(IC2-VREF-{slash}CVREF-{slash}AERXD2{slash}PMA7{slash}RA9-Pad28)") (class "Default")
      (node (ref "IC2") (pin "28") (pinfunction "VREF-/CVREF-/AERXD2/PMA7/RA9_28") (pintype "bidirectional"))
    )
    (net (code "188") (name "unconnected-(IC7-NC1-Pad1)") (class "Default")
      (node (ref "IC7") (pin "1") (pinfunction "NC1_1") (pintype "bidirectional"))
    )
    (net (code "189") (name "unconnected-(IC7-NC2-Pad2)") (class "Default")
      (node (ref "IC7") (pin "2") (pinfunction "NC2_2") (pintype "bidirectional"))
    )
    (net (code "190") (name "unconnected-(IC8-NC1-Pad1)") (class "Default")
      (node (ref "IC8") (pin "1") (pinfunction "NC1_1") (pintype "bidirectional"))
    )
    (net (code "191") (name "unconnected-(IC8-NC2-Pad2)") (class "Default")
      (node (ref "IC8") (pin "2") (pinfunction "NC2_2") (pintype "bidirectional"))
    )
    (net (code "192") (name "unconnected-(IC9-VREF-Pad5)") (class "Default")
      (node (ref "IC9") (pin "5") (pinfunction "VREF_5") (pintype "bidirectional"))
    )
    (net (code "193") (name "unconnected-(IC9-VSS-Pad2)") (class "Default")
      (node (ref "IC9") (pin "2") (pinfunction "VSS_2") (pintype "bidirectional"))
    )
    (net (code "194") (name "unconnected-(IC11-VREF-Pad5)") (class "Default")
      (node (ref "IC11") (pin "5") (pinfunction "VREF_5") (pintype "bidirectional"))
    )
    (net (code "195") (name "unconnected-(IC13A-R1IN-Pad13)") (class "Default")
      (node (ref "IC13") (pin "13") (pinfunction "R1IN_13") (pintype "input"))
    )
    (net (code "196") (name "unconnected-(IC13A-R1OUT-Pad12)") (class "Default")
      (node (ref "IC13") (pin "12") (pinfunction "R1OUT_12") (pintype "output"))
    )
    (net (code "197") (name "unconnected-(IC13A-T1IN-Pad11)") (class "Default")
      (node (ref "IC13") (pin "11") (pinfunction "T1IN_11") (pintype "input"))
    )
    (net (code "198") (name "unconnected-(IC13A-T1OUT-Pad14)") (class "Default")
      (node (ref "IC13") (pin "14") (pinfunction "T1OUT_14") (pintype "output"))
    )
  )
)
